# sboardnew.net
KiCad netlist of a schematic drawn in EAGLE
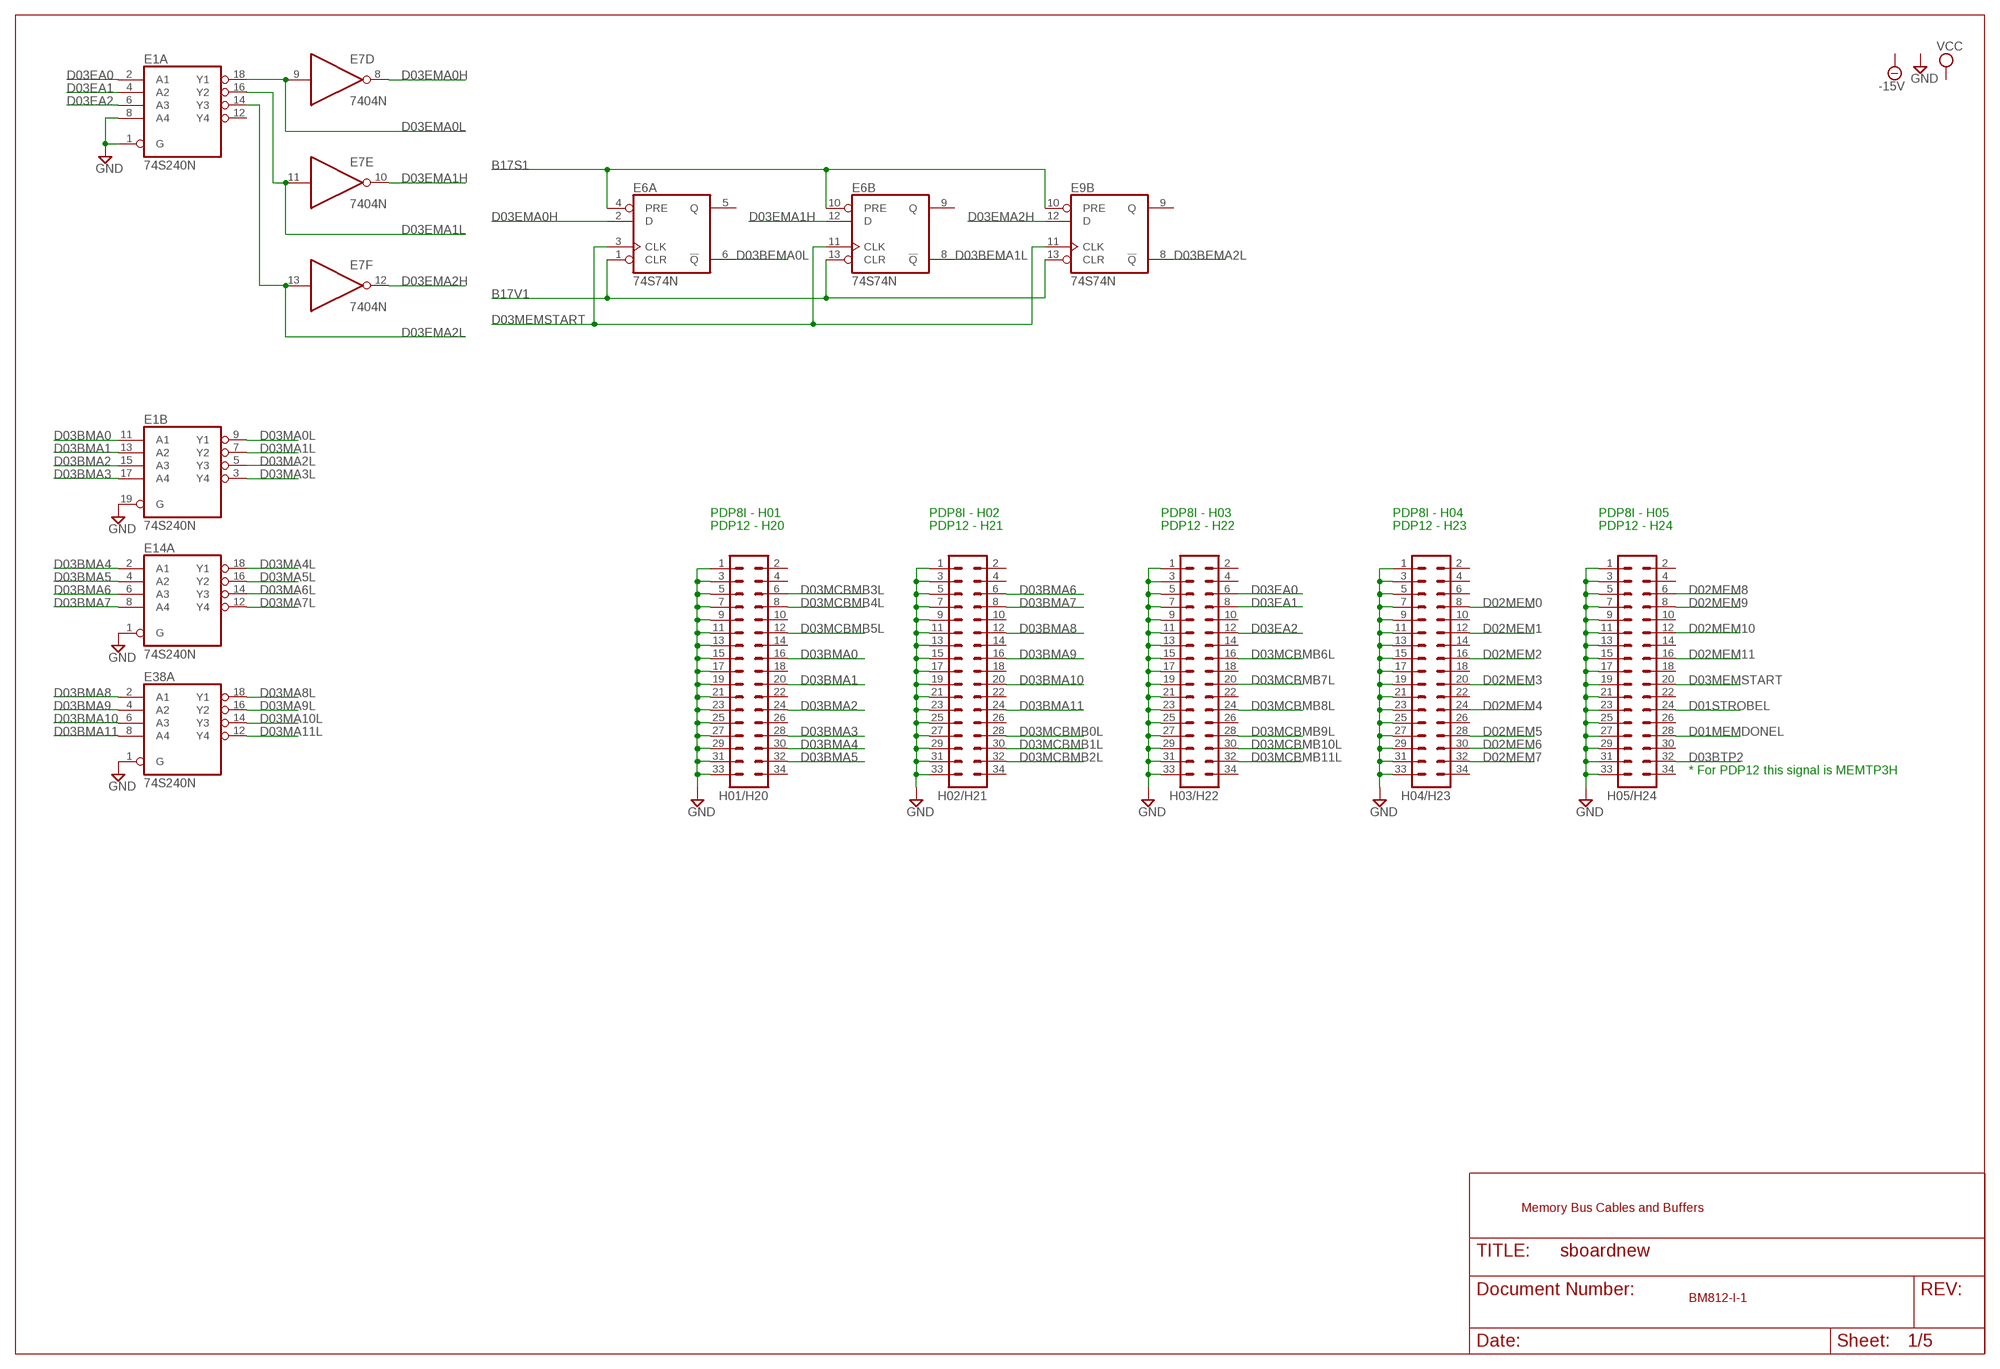
[diagram p0: schematic, sheet 1]
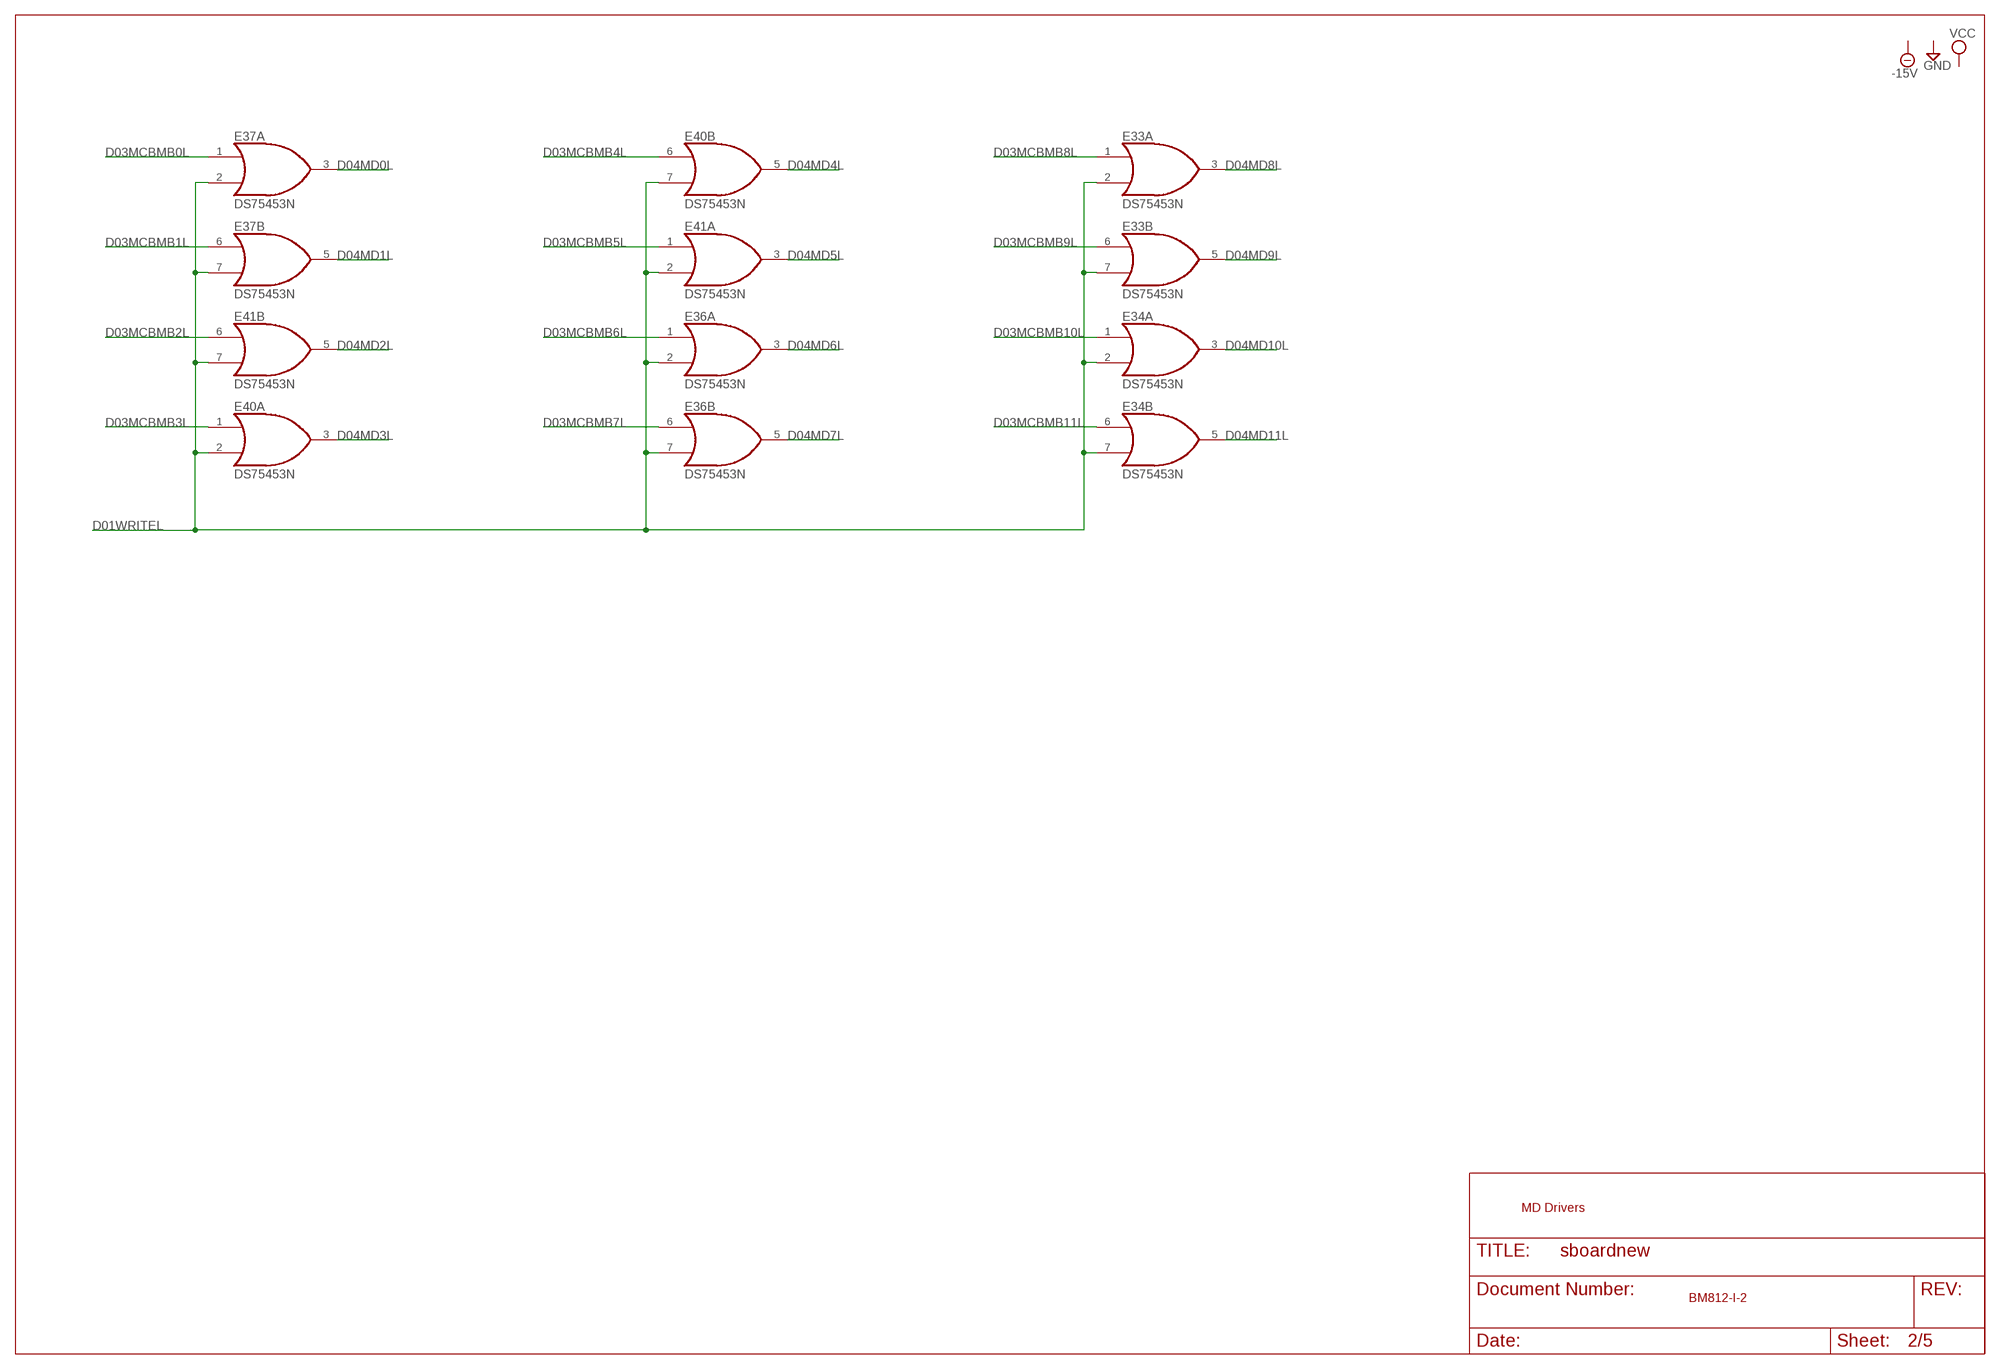
[diagram p1: schematic, sheet 2]
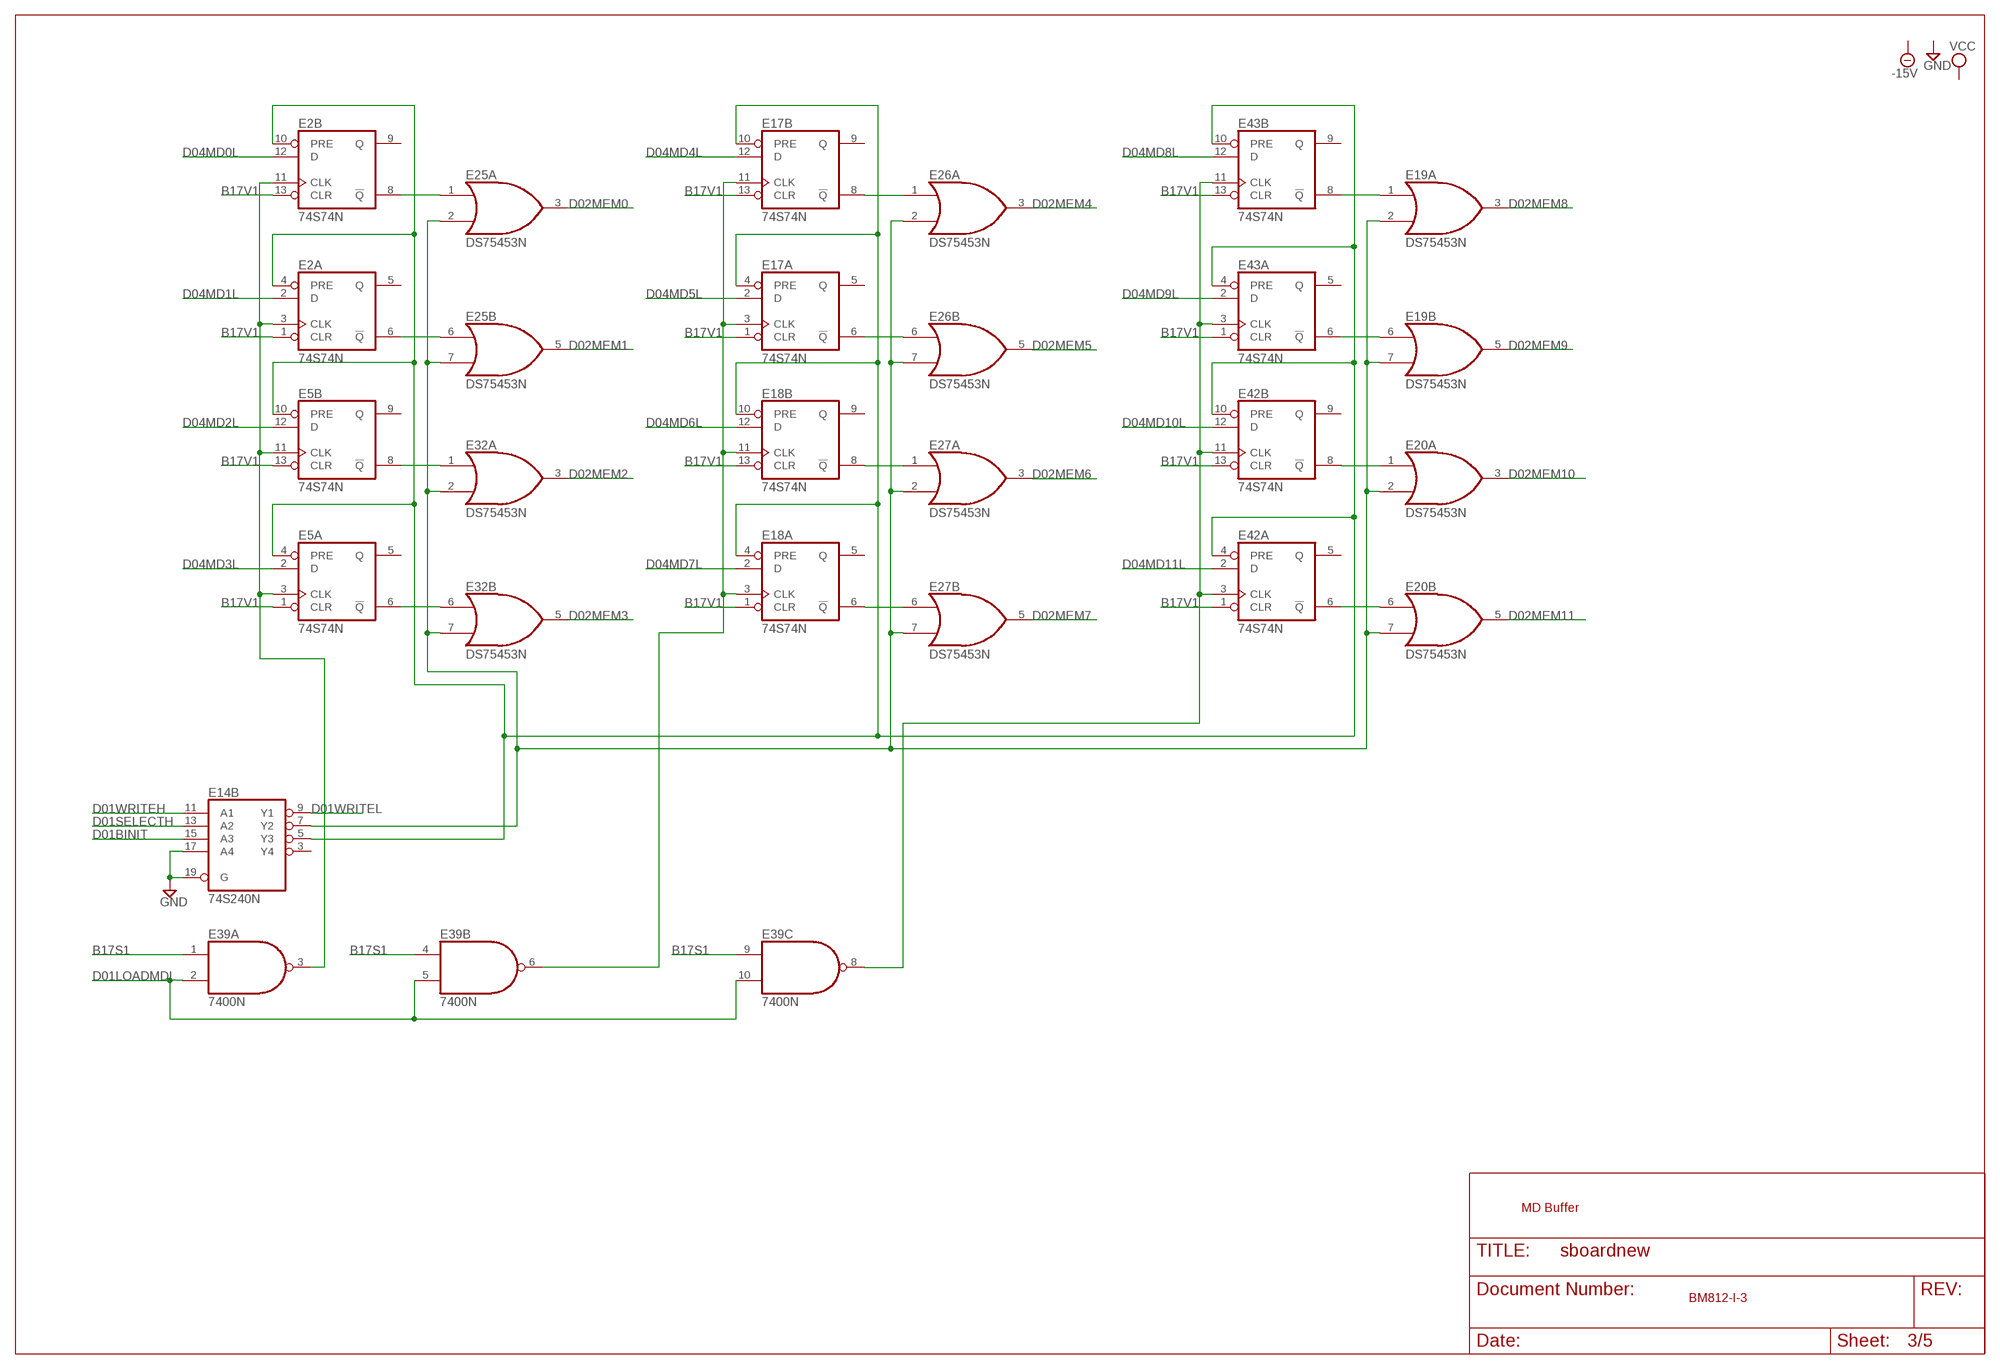
[diagram p2: schematic, sheet 3]
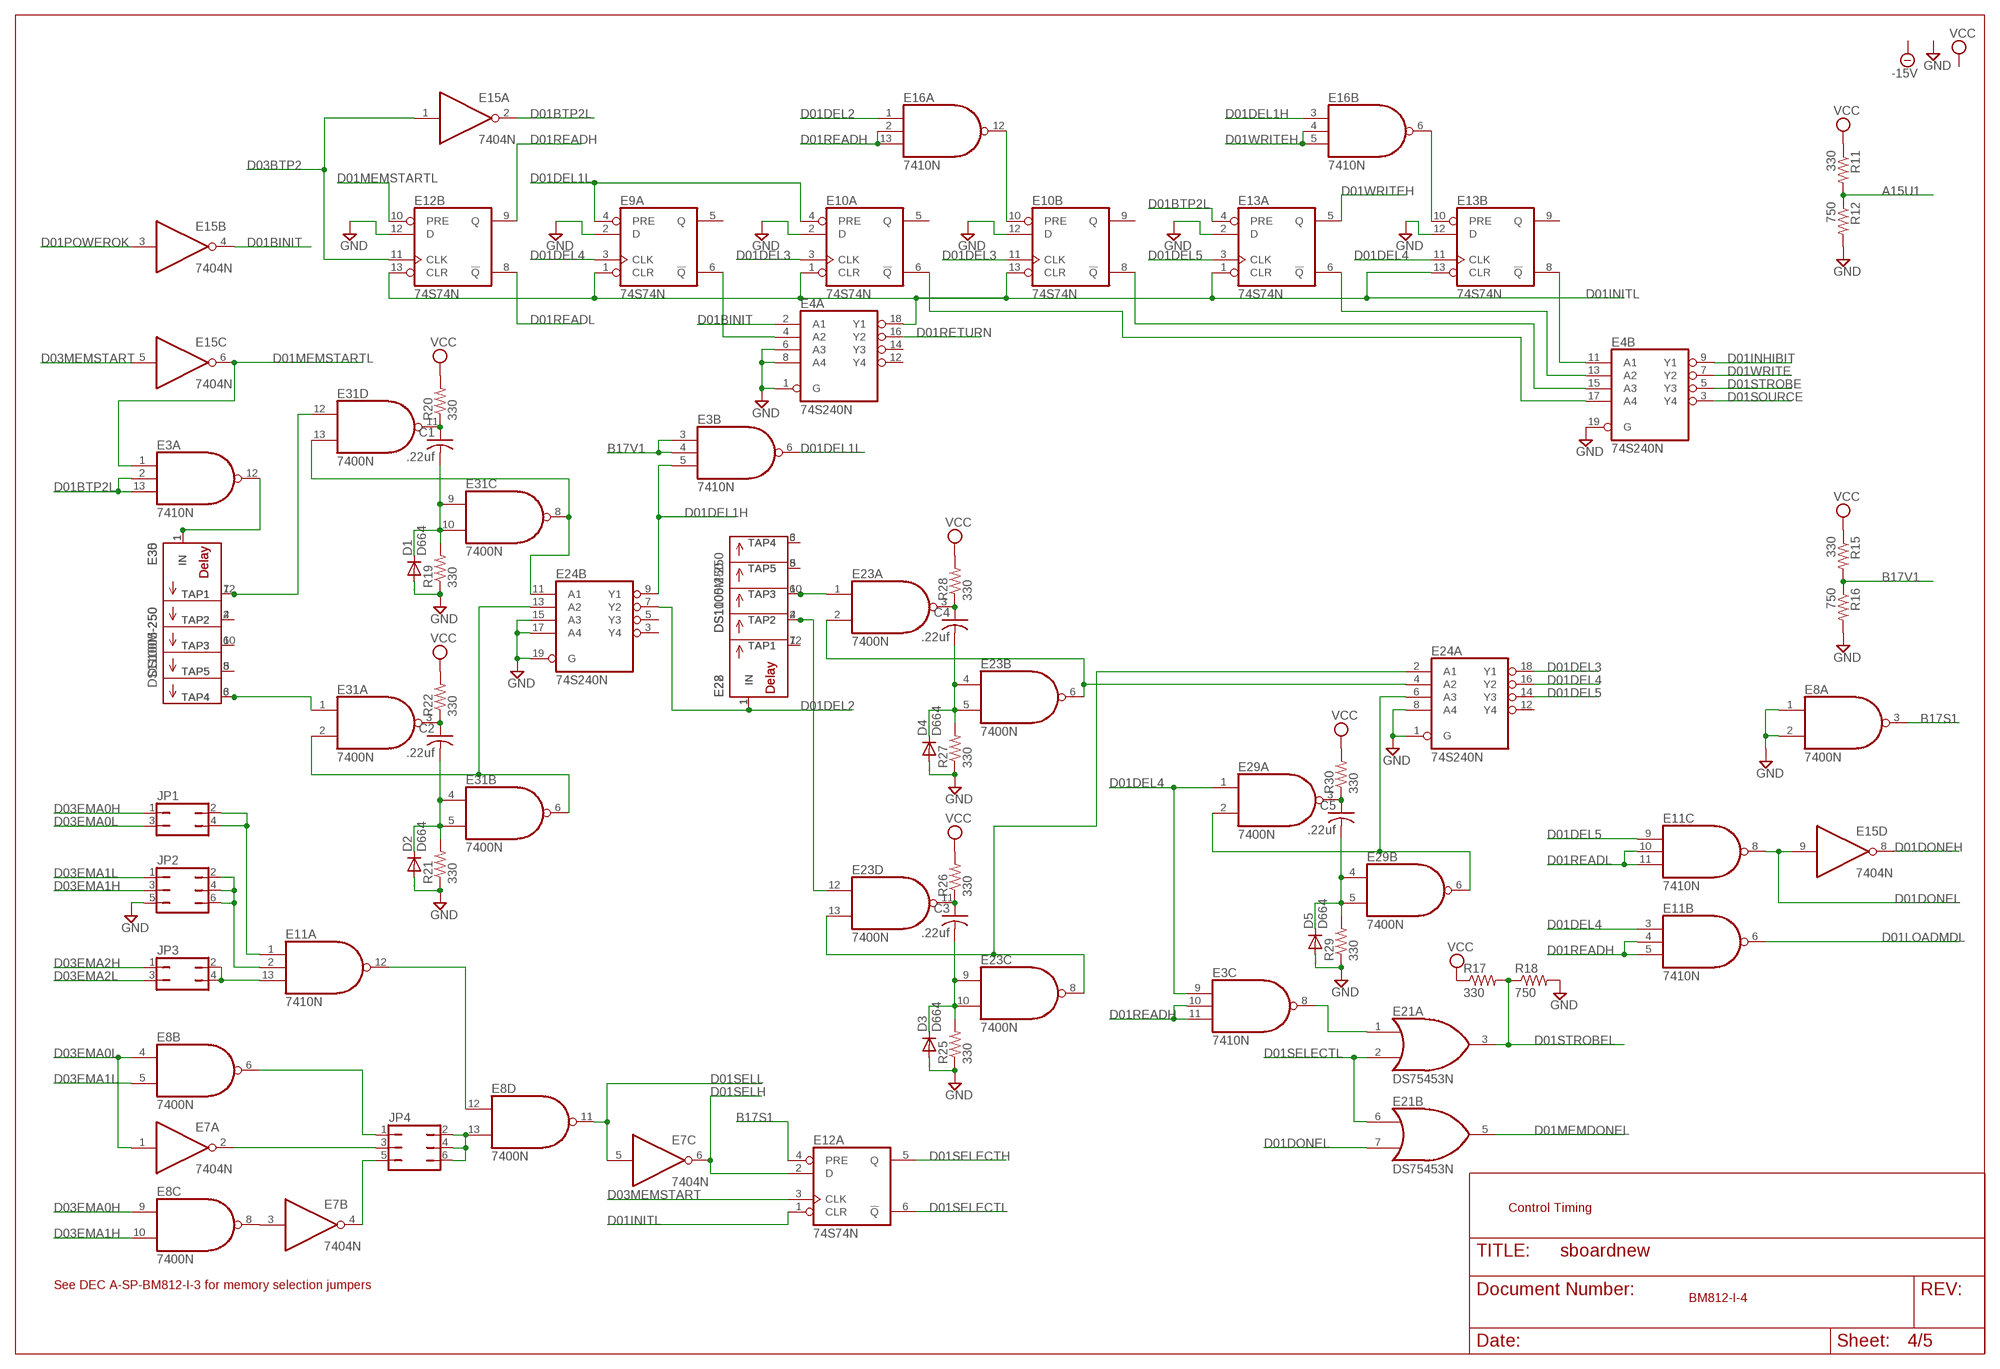
[diagram p3: schematic, sheet 4]
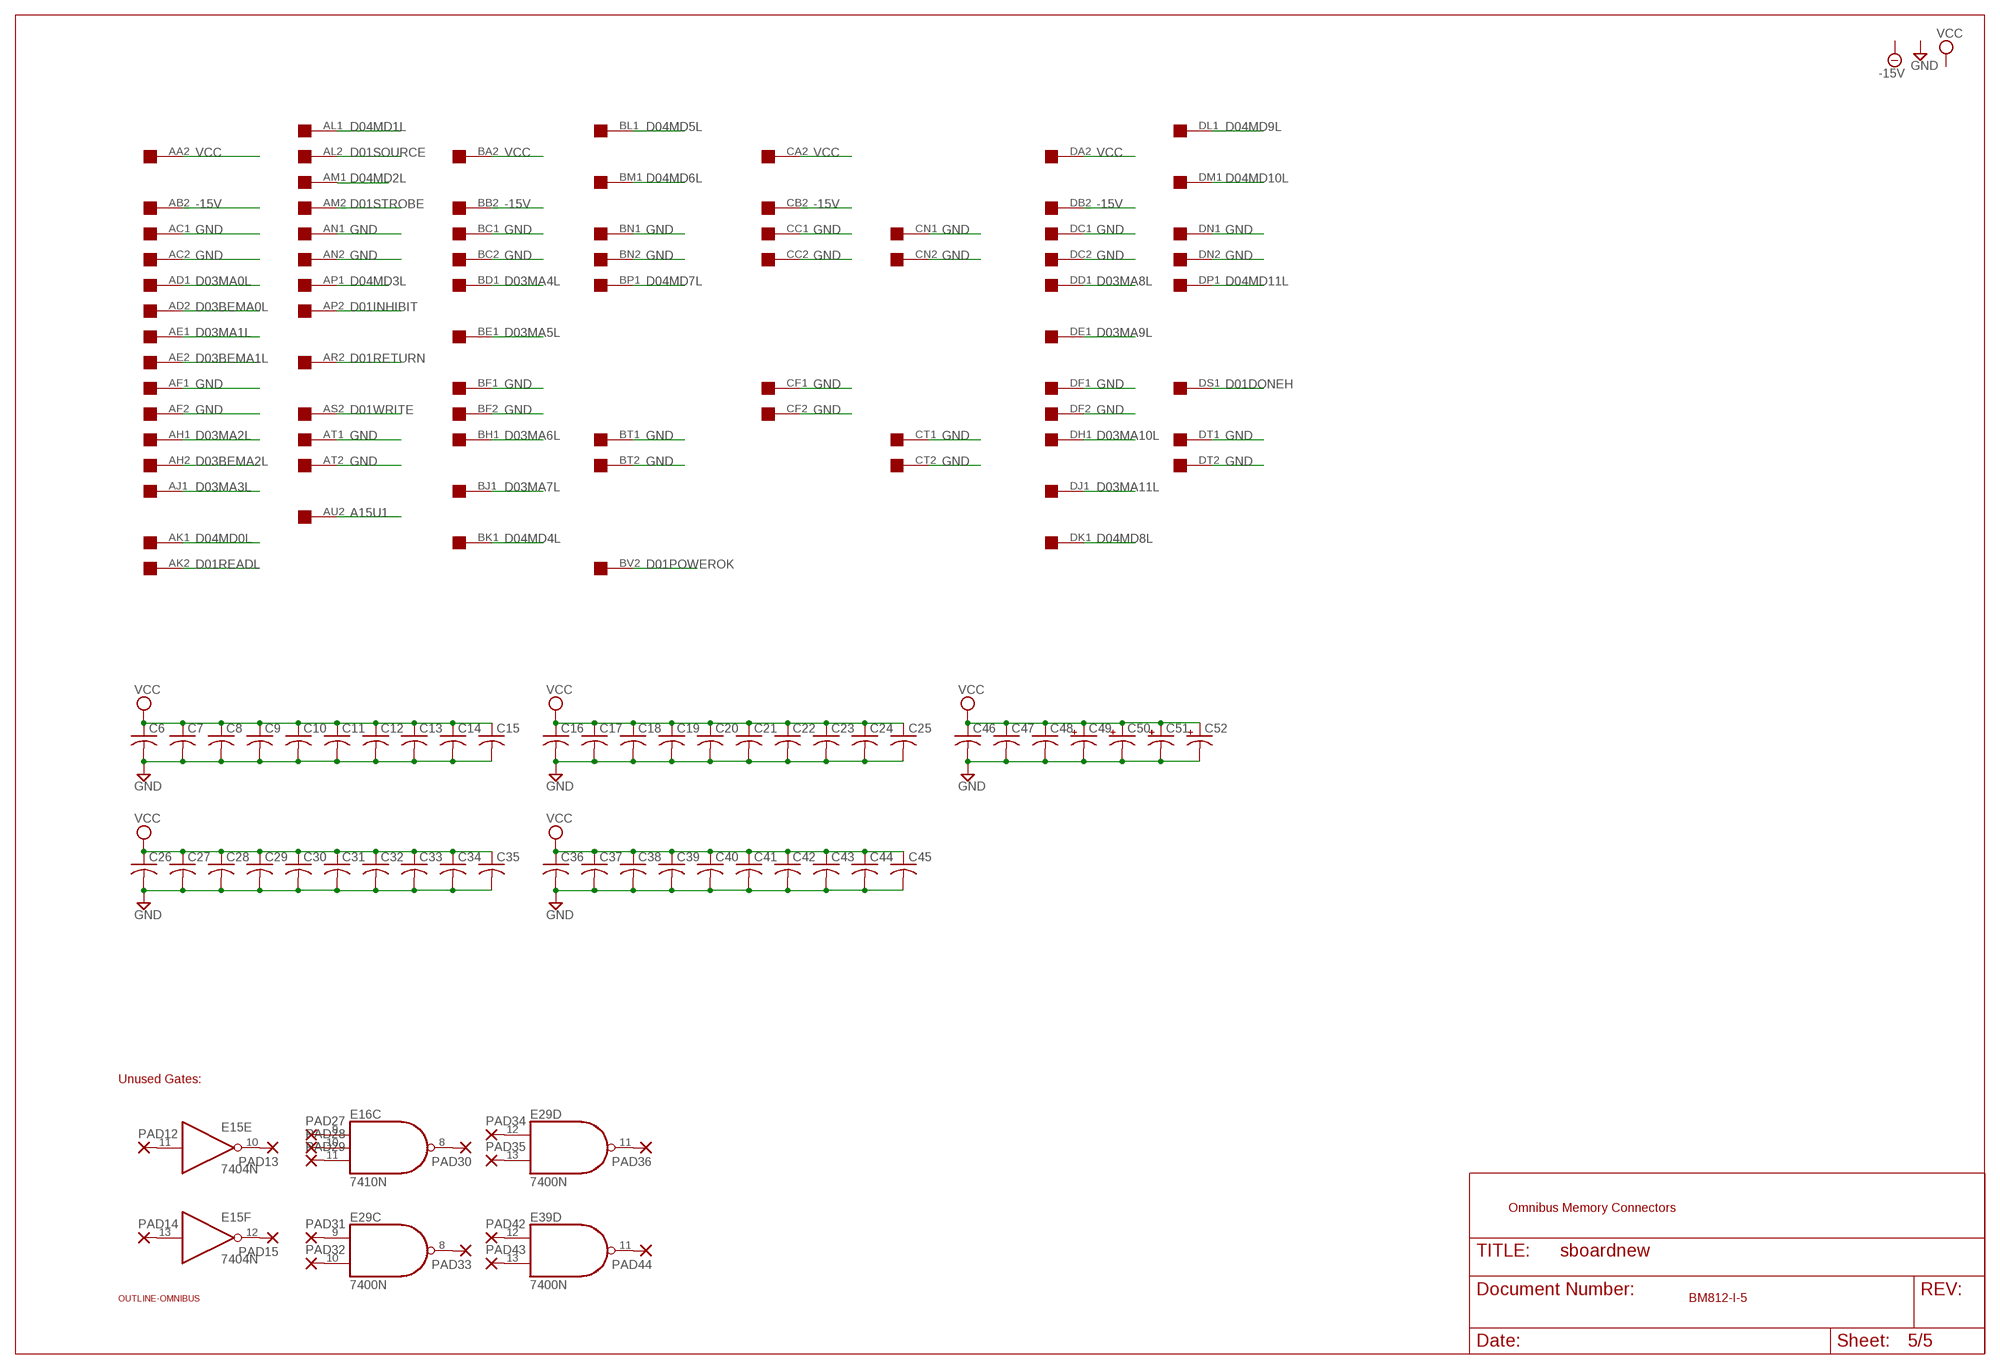
[diagram p4: schematic, sheet 5]

(export (version "E")
  (design (tool "Eeschema 10.0.6"))
  (components
    (comp (ref "E33")
      (value "DS75453N")
      (footprint "eagle-import:DIL08")
      (libsource (lib "eagle-import") (part "DS75453N"))
    )
    (comp (ref "E34")
      (value "DS75453N")
      (footprint "eagle-import:DIL08")
      (libsource (lib "eagle-import") (part "DS75453N"))
    )
    (comp (ref "E36")
      (value "DS75453N")
      (footprint "eagle-import:DIL08")
      (libsource (lib "eagle-import") (part "DS75453N"))
    )
    (comp (ref "E37")
      (value "DS75453N")
      (footprint "eagle-import:DIL08")
      (libsource (lib "eagle-import") (part "DS75453N"))
    )
    (comp (ref "E40")
      (value "DS75453N")
      (footprint "eagle-import:DIL08")
      (libsource (lib "eagle-import") (part "DS75453N"))
    )
    (comp (ref "E41")
      (value "DS75453N")
      (footprint "eagle-import:DIL08")
      (libsource (lib "eagle-import") (part "DS75453N"))
    )
    (comp (ref "E2")
      (value "74S74N")
      (footprint "eagle-import:DIL14")
      (libsource (lib "eagle-import") (part "7474NS"))
    )
    (comp (ref "E5")
      (value "74S74N")
      (footprint "eagle-import:DIL14")
      (libsource (lib "eagle-import") (part "7474NS"))
    )
    (comp (ref "E14")
      (value "74S240N")
      (footprint "eagle-import:DIL20")
      (libsource (lib "eagle-import") (part "74240NS"))
    )
    (comp (ref "E17")
      (value "74S74N")
      (footprint "eagle-import:DIL14")
      (libsource (lib "eagle-import") (part "7474NS"))
    )
    (comp (ref "E18")
      (value "74S74N")
      (footprint "eagle-import:DIL14")
      (libsource (lib "eagle-import") (part "7474NS"))
    )
    (comp (ref "E19")
      (value "DS75453N")
      (footprint "eagle-import:DIL08")
      (libsource (lib "eagle-import") (part "DS75453N"))
    )
    (comp (ref "E20")
      (value "DS75453N")
      (footprint "eagle-import:DIL08")
      (libsource (lib "eagle-import") (part "DS75453N"))
    )
    (comp (ref "E25")
      (value "DS75453N")
      (footprint "eagle-import:DIL08")
      (libsource (lib "eagle-import") (part "DS75453N"))
    )
    (comp (ref "E26")
      (value "DS75453N")
      (footprint "eagle-import:DIL08")
      (libsource (lib "eagle-import") (part "DS75453N"))
    )
    (comp (ref "E27")
      (value "DS75453N")
      (footprint "eagle-import:DIL08")
      (libsource (lib "eagle-import") (part "DS75453N"))
    )
    (comp (ref "E32")
      (value "DS75453N")
      (footprint "eagle-import:DIL08")
      (libsource (lib "eagle-import") (part "DS75453N"))
    )
    (comp (ref "E39")
      (value "7400N")
      (footprint "eagle-import:DIL14")
      (libsource (lib "eagle-import") (part "7400N"))
    )
    (comp (ref "E42")
      (value "74S74N")
      (footprint "eagle-import:DIL14")
      (libsource (lib "eagle-import") (part "7474NS"))
    )
    (comp (ref "E43")
      (value "74S74N")
      (footprint "eagle-import:DIL14")
      (libsource (lib "eagle-import") (part "7474NS"))
    )
    (comp (ref "C6")
      (value "C-US050-025X075")
      (footprint "eagle-import:C050-025X075")
      (libsource (lib "eagle-import") (part "C-US050-025X075"))
    )
    (comp (ref "C7")
      (value "C-US050-025X075")
      (footprint "eagle-import:C050-025X075")
      (libsource (lib "eagle-import") (part "C-US050-025X075"))
    )
    (comp (ref "C8")
      (value "C-US050-025X075")
      (footprint "eagle-import:C050-025X075")
      (libsource (lib "eagle-import") (part "C-US050-025X075"))
    )
    (comp (ref "C9")
      (value "C-US050-025X075")
      (footprint "eagle-import:C050-025X075")
      (libsource (lib "eagle-import") (part "C-US050-025X075"))
    )
    (comp (ref "C10")
      (value "C-US050-025X075")
      (footprint "eagle-import:C050-025X075")
      (libsource (lib "eagle-import") (part "C-US050-025X075"))
    )
    (comp (ref "C11")
      (value "C-US050-025X075")
      (footprint "eagle-import:C050-025X075")
      (libsource (lib "eagle-import") (part "C-US050-025X075"))
    )
    (comp (ref "C12")
      (value "C-US050-025X075")
      (footprint "eagle-import:C050-025X075")
      (libsource (lib "eagle-import") (part "C-US050-025X075"))
    )
    (comp (ref "C13")
      (value "C-US050-025X075")
      (footprint "eagle-import:C050-025X075")
      (libsource (lib "eagle-import") (part "C-US050-025X075"))
    )
    (comp (ref "C14")
      (value "C-US050-025X075")
      (footprint "eagle-import:C050-025X075")
      (libsource (lib "eagle-import") (part "C-US050-025X075"))
    )
    (comp (ref "C15")
      (value "C-US050-025X075")
      (footprint "eagle-import:C050-025X075")
      (libsource (lib "eagle-import") (part "C-US050-025X075"))
    )
    (comp (ref "C16")
      (value "C-US050-025X075")
      (footprint "eagle-import:C050-025X075")
      (libsource (lib "eagle-import") (part "C-US050-025X075"))
    )
    (comp (ref "C17")
      (value "C-US050-025X075")
      (footprint "eagle-import:C050-025X075")
      (libsource (lib "eagle-import") (part "C-US050-025X075"))
    )
    (comp (ref "C18")
      (value "C-US050-025X075")
      (footprint "eagle-import:C050-025X075")
      (libsource (lib "eagle-import") (part "C-US050-025X075"))
    )
    (comp (ref "C19")
      (value "C-US050-025X075")
      (footprint "eagle-import:C050-025X075")
      (libsource (lib "eagle-import") (part "C-US050-025X075"))
    )
    (comp (ref "C20")
      (value "C-US050-025X075")
      (footprint "eagle-import:C050-025X075")
      (libsource (lib "eagle-import") (part "C-US050-025X075"))
    )
    (comp (ref "C21")
      (value "C-US050-025X075")
      (footprint "eagle-import:C050-025X075")
      (libsource (lib "eagle-import") (part "C-US050-025X075"))
    )
    (comp (ref "C22")
      (value "C-US050-025X075")
      (footprint "eagle-import:C050-025X075")
      (libsource (lib "eagle-import") (part "C-US050-025X075"))
    )
    (comp (ref "C23")
      (value "C-US050-025X075")
      (footprint "eagle-import:C050-025X075")
      (libsource (lib "eagle-import") (part "C-US050-025X075"))
    )
    (comp (ref "C24")
      (value "C-US050-025X075")
      (footprint "eagle-import:C050-025X075")
      (libsource (lib "eagle-import") (part "C-US050-025X075"))
    )
    (comp (ref "C25")
      (value "C-US050-025X075")
      (footprint "eagle-import:C050-025X075")
      (libsource (lib "eagle-import") (part "C-US050-025X075"))
    )
    (comp (ref "C26")
      (value "C-US050-025X075")
      (footprint "eagle-import:C050-025X075")
      (libsource (lib "eagle-import") (part "C-US050-025X075"))
    )
    (comp (ref "C27")
      (value "C-US050-025X075")
      (footprint "eagle-import:C050-025X075")
      (libsource (lib "eagle-import") (part "C-US050-025X075"))
    )
    (comp (ref "C28")
      (value "C-US050-025X075")
      (footprint "eagle-import:C050-025X075")
      (libsource (lib "eagle-import") (part "C-US050-025X075"))
    )
    (comp (ref "C29")
      (value "C-US050-025X075")
      (footprint "eagle-import:C050-025X075")
      (libsource (lib "eagle-import") (part "C-US050-025X075"))
    )
    (comp (ref "C30")
      (value "C-US050-025X075")
      (footprint "eagle-import:C050-025X075")
      (libsource (lib "eagle-import") (part "C-US050-025X075"))
    )
    (comp (ref "C31")
      (value "C-US050-025X075")
      (footprint "eagle-import:C050-025X075")
      (libsource (lib "eagle-import") (part "C-US050-025X075"))
    )
    (comp (ref "C32")
      (value "C-US050-025X075")
      (footprint "eagle-import:C050-025X075")
      (libsource (lib "eagle-import") (part "C-US050-025X075"))
    )
    (comp (ref "C33")
      (value "C-US050-025X075")
      (footprint "eagle-import:C050-025X075")
      (libsource (lib "eagle-import") (part "C-US050-025X075"))
    )
    (comp (ref "C34")
      (value "C-US050-025X075")
      (footprint "eagle-import:C050-025X075")
      (libsource (lib "eagle-import") (part "C-US050-025X075"))
    )
    (comp (ref "C35")
      (value "C-US050-025X075")
      (footprint "eagle-import:C050-025X075")
      (libsource (lib "eagle-import") (part "C-US050-025X075"))
    )
    (comp (ref "C36")
      (value "C-US050-025X075")
      (footprint "eagle-import:C050-025X075")
      (libsource (lib "eagle-import") (part "C-US050-025X075"))
    )
    (comp (ref "C37")
      (value "C-US050-025X075")
      (footprint "eagle-import:C050-025X075")
      (libsource (lib "eagle-import") (part "C-US050-025X075"))
    )
    (comp (ref "C38")
      (value "C-US050-025X075")
      (footprint "eagle-import:C050-025X075")
      (libsource (lib "eagle-import") (part "C-US050-025X075"))
    )
    (comp (ref "C39")
      (value "C-US050-025X075")
      (footprint "eagle-import:C050-025X075")
      (libsource (lib "eagle-import") (part "C-US050-025X075"))
    )
    (comp (ref "C40")
      (value "C-US050-025X075")
      (footprint "eagle-import:C050-025X075")
      (libsource (lib "eagle-import") (part "C-US050-025X075"))
    )
    (comp (ref "C41")
      (value "C-US050-025X075")
      (footprint "eagle-import:C050-025X075")
      (libsource (lib "eagle-import") (part "C-US050-025X075"))
    )
    (comp (ref "C42")
      (value "C-US050-025X075")
      (footprint "eagle-import:C050-025X075")
      (libsource (lib "eagle-import") (part "C-US050-025X075"))
    )
    (comp (ref "C43")
      (value "C-US050-025X075")
      (footprint "eagle-import:C050-025X075")
      (libsource (lib "eagle-import") (part "C-US050-025X075"))
    )
    (comp (ref "C44")
      (value "C-US050-025X075")
      (footprint "eagle-import:C050-025X075")
      (libsource (lib "eagle-import") (part "C-US050-025X075"))
    )
    (comp (ref "C45")
      (value "C-US050-025X075")
      (footprint "eagle-import:C050-025X075")
      (libsource (lib "eagle-import") (part "C-US050-025X075"))
    )
    (comp (ref "C46")
      (value "C-US050-025X075")
      (footprint "eagle-import:C050-025X075")
      (libsource (lib "eagle-import") (part "C-US050-025X075"))
    )
    (comp (ref "C47")
      (value "C-US050-025X075")
      (footprint "eagle-import:C050-025X075")
      (libsource (lib "eagle-import") (part "C-US050-025X075"))
    )
    (comp (ref "C48")
      (value "C-US050-025X075")
      (footprint "eagle-import:C050-025X075")
      (libsource (lib "eagle-import") (part "C-US050-025X075"))
    )
    (comp (ref "C49")
      (value "CPOL-USE22-6AXIAL")
      (footprint "eagle-import:E22-6")
      (libsource (lib "eagle-import") (part "CPOL-USE22-6AXIAL"))
    )
    (comp (ref "C50")
      (value "CPOL-USE22-6AXIAL")
      (footprint "eagle-import:E22-6")
      (libsource (lib "eagle-import") (part "CPOL-USE22-6AXIAL"))
    )
    (comp (ref "C51")
      (value "CPOL-USE22-6AXIAL")
      (footprint "eagle-import:E22-6")
      (libsource (lib "eagle-import") (part "CPOL-USE22-6AXIAL"))
    )
    (comp (ref "C52")
      (value "CPOL-USE22-6AXIAL")
      (footprint "eagle-import:E22-6")
      (libsource (lib "eagle-import") (part "CPOL-USE22-6AXIAL"))
    )
    (comp (ref "E15")
      (value "7404N")
      (footprint "eagle-import:DIL14")
      (libsource (lib "eagle-import") (part "7404N"))
    )
    (comp (ref "E16")
      (value "7410N")
      (footprint "eagle-import:DIL14")
      (libsource (lib "eagle-import") (part "7410N"))
    )
    (comp (ref "E29")
      (value "7400N")
      (footprint "eagle-import:DIL14")
      (libsource (lib "eagle-import") (part "7400N"))
    )
    (comp (ref "PAD12")
      (value "1,6/0,8")
      (footprint "eagle-import:1,6_0,8")
      (libsource (lib "eagle-import") (part "1,6/0,8"))
    )
    (comp (ref "PAD13")
      (value "1,6/0,8")
      (footprint "eagle-import:1,6_0,8")
      (libsource (lib "eagle-import") (part "1,6/0,8"))
    )
    (comp (ref "PAD14")
      (value "1,6/0,8")
      (footprint "eagle-import:1,6_0,8")
      (libsource (lib "eagle-import") (part "1,6/0,8"))
    )
    (comp (ref "PAD15")
      (value "1,6/0,8")
      (footprint "eagle-import:1,6_0,8")
      (libsource (lib "eagle-import") (part "1,6/0,8"))
    )
    (comp (ref "PAD27")
      (value "1,6/0,8")
      (footprint "eagle-import:1,6_0,8")
      (libsource (lib "eagle-import") (part "1,6/0,8"))
    )
    (comp (ref "PAD28")
      (value "1,6/0,8")
      (footprint "eagle-import:1,6_0,8")
      (libsource (lib "eagle-import") (part "1,6/0,8"))
    )
    (comp (ref "PAD29")
      (value "1,6/0,8")
      (footprint "eagle-import:1,6_0,8")
      (libsource (lib "eagle-import") (part "1,6/0,8"))
    )
    (comp (ref "PAD30")
      (value "1,6/0,8")
      (footprint "eagle-import:1,6_0,8")
      (libsource (lib "eagle-import") (part "1,6/0,8"))
    )
    (comp (ref "PAD31")
      (value "1,6/0,8")
      (footprint "eagle-import:1,6_0,8")
      (libsource (lib "eagle-import") (part "1,6/0,8"))
    )
    (comp (ref "PAD32")
      (value "1,6/0,8")
      (footprint "eagle-import:1,6_0,8")
      (libsource (lib "eagle-import") (part "1,6/0,8"))
    )
    (comp (ref "PAD33")
      (value "1,6/0,8")
      (footprint "eagle-import:1,6_0,8")
      (libsource (lib "eagle-import") (part "1,6/0,8"))
    )
    (comp (ref "PAD34")
      (value "1,6/0,8")
      (footprint "eagle-import:1,6_0,8")
      (libsource (lib "eagle-import") (part "1,6/0,8"))
    )
    (comp (ref "PAD35")
      (value "1,6/0,8")
      (footprint "eagle-import:1,6_0,8")
      (libsource (lib "eagle-import") (part "1,6/0,8"))
    )
    (comp (ref "PAD36")
      (value "1,6/0,8")
      (footprint "eagle-import:1,6_0,8")
      (libsource (lib "eagle-import") (part "1,6/0,8"))
    )
    (comp (ref "PAD42")
      (value "1,6/0,8")
      (footprint "eagle-import:1,6_0,8")
      (libsource (lib "eagle-import") (part "1,6/0,8"))
    )
    (comp (ref "PAD43")
      (value "1,6/0,8")
      (footprint "eagle-import:1,6_0,8")
      (libsource (lib "eagle-import") (part "1,6/0,8"))
    )
    (comp (ref "PAD44")
      (value "1,6/0,8")
      (footprint "eagle-import:1,6_0,8")
      (libsource (lib "eagle-import") (part "1,6/0,8"))
    )
    (comp (ref "U$1")
      (value "QUAD")
      (footprint "eagle-import:EDGE-CON8")
      (libsource (lib "eagle-import") (part "QUAD"))
    )
    (comp (ref "U$2")
      (value "OUTLINE-OMNIBUS")
      (footprint "eagle-import:OMNIBUS")
      (libsource (lib "eagle-import") (part "OUTLINE-OMNIBUS"))
    )
    (comp (ref "C1")
      (value ".22uf")
      (footprint "eagle-import:C050-025X075")
      (libsource (lib "eagle-import") (part "C-US050-025X075"))
    )
    (comp (ref "C2")
      (value ".22uf")
      (footprint "eagle-import:C050-025X075")
      (libsource (lib "eagle-import") (part "C-US050-025X075"))
    )
    (comp (ref "C3")
      (value ".22uf")
      (footprint "eagle-import:C050-025X075")
      (libsource (lib "eagle-import") (part "C-US050-025X075"))
    )
    (comp (ref "C4")
      (value ".22uf")
      (footprint "eagle-import:C050-025X075")
      (libsource (lib "eagle-import") (part "C-US050-025X075"))
    )
    (comp (ref "C5")
      (value ".22uf")
      (footprint "eagle-import:C050-025X075")
      (libsource (lib "eagle-import") (part "C-US050-025X075"))
    )
    (comp (ref "D1")
      (value "D664")
      (footprint "eagle-import:DO35-10")
      (libsource (lib "eagle-import") (part "1N4148DO35-10"))
    )
    (comp (ref "D2")
      (value "D664")
      (footprint "eagle-import:DO35-10")
      (libsource (lib "eagle-import") (part "1N4148DO35-10"))
    )
    (comp (ref "D3")
      (value "D664")
      (footprint "eagle-import:DO35-10")
      (libsource (lib "eagle-import") (part "1N4148DO35-10"))
    )
    (comp (ref "D4")
      (value "D664")
      (footprint "eagle-import:DO35-10")
      (libsource (lib "eagle-import") (part "1N4148DO35-10"))
    )
    (comp (ref "D5")
      (value "D664")
      (footprint "eagle-import:DO35-10")
      (libsource (lib "eagle-import") (part "1N4148DO35-10"))
    )
    (comp (ref "E3")
      (value "7410N")
      (footprint "eagle-import:DIL14")
      (libsource (lib "eagle-import") (part "7410N"))
    )
    (comp (ref "E4")
      (value "74S240N")
      (footprint "eagle-import:DIL20")
      (libsource (lib "eagle-import") (part "74240NS"))
    )
    (comp (ref "E7")
      (value "7404N")
      (footprint "eagle-import:DIL14")
      (libsource (lib "eagle-import") (part "7404N"))
    )
    (comp (ref "E8")
      (value "7400N")
      (footprint "eagle-import:DIL14")
      (libsource (lib "eagle-import") (part "7400N"))
    )
    (comp (ref "E9")
      (value "74S74N")
      (footprint "eagle-import:DIL14")
      (libsource (lib "eagle-import") (part "7474NS"))
    )
    (comp (ref "E10")
      (value "74S74N")
      (footprint "eagle-import:DIL14")
      (libsource (lib "eagle-import") (part "7474NS"))
    )
    (comp (ref "E11")
      (value "7410N")
      (footprint "eagle-import:DIL14")
      (libsource (lib "eagle-import") (part "7410N"))
    )
    (comp (ref "E12")
      (value "74S74N")
      (footprint "eagle-import:DIL14")
      (libsource (lib "eagle-import") (part "7474NS"))
    )
    (comp (ref "E13")
      (value "74S74N")
      (footprint "eagle-import:DIL14")
      (libsource (lib "eagle-import") (part "7474NS"))
    )
    (comp (ref "E21")
      (value "DS75453N")
      (footprint "eagle-import:DIL08")
      (libsource (lib "eagle-import") (part "DS75453N"))
    )
    (comp (ref "E22")
      (value "DS1100M-250")
      (footprint "eagle-import:DIL08")
      (libsource (lib "eagle-import") (part "MXD1000"))
    )
    (comp (ref "E23")
      (value "7400N")
      (footprint "eagle-import:DIL14")
      (libsource (lib "eagle-import") (part "7400N"))
    )
    (comp (ref "E24")
      (value "74S240N")
      (footprint "eagle-import:DIL20")
      (libsource (lib "eagle-import") (part "74240NS"))
    )
    (comp (ref "E28")
      (value "DS1005-250")
      (footprint "eagle-import:DIL14")
      (libsource (lib "eagle-import") (part "MXD1000P"))
    )
    (comp (ref "E30")
      (value "DS1005-250")
      (footprint "eagle-import:DIL14")
      (libsource (lib "eagle-import") (part "MXD1000P"))
    )
    (comp (ref "E31")
      (value "7400N")
      (footprint "eagle-import:DIL14")
      (libsource (lib "eagle-import") (part "7400N"))
    )
    (comp (ref "E35")
      (value "DS1100M-250")
      (footprint "eagle-import:DIL08")
      (libsource (lib "eagle-import") (part "MXD1000"))
    )
    (comp (ref "JP1")
      (value "JP2Q")
      (footprint "eagle-import:JP2Q")
      (libsource (lib "eagle-import") (part "JP2Q"))
    )
    (comp (ref "JP2")
      (value "JP3Q")
      (footprint "eagle-import:JP3Q")
      (libsource (lib "eagle-import") (part "JP3Q"))
    )
    (comp (ref "JP3")
      (value "JP2Q")
      (footprint "eagle-import:JP2Q")
      (libsource (lib "eagle-import") (part "JP2Q"))
    )
    (comp (ref "JP4")
      (value "JP3Q")
      (footprint "eagle-import:JP3Q")
      (libsource (lib "eagle-import") (part "JP3Q"))
    )
    (comp (ref "R11")
      (value "330")
      (footprint "eagle-import:0207_10")
      (libsource (lib "eagle-import") (part "R-US_0207/10"))
    )
    (comp (ref "R12")
      (value "750")
      (footprint "eagle-import:0207_10")
      (libsource (lib "eagle-import") (part "R-US_0207/10"))
    )
    (comp (ref "R15")
      (value "330")
      (footprint "eagle-import:0207_10")
      (libsource (lib "eagle-import") (part "R-US_0207/10"))
    )
    (comp (ref "R16")
      (value "750")
      (footprint "eagle-import:0207_10")
      (libsource (lib "eagle-import") (part "R-US_0207/10"))
    )
    (comp (ref "R17")
      (value "330")
      (footprint "eagle-import:0207_10")
      (libsource (lib "eagle-import") (part "R-US_0207/10"))
    )
    (comp (ref "R18")
      (value "750")
      (footprint "eagle-import:0207_10")
      (libsource (lib "eagle-import") (part "R-US_0207/10"))
    )
    (comp (ref "R19")
      (value "330")
      (footprint "eagle-import:0207_10")
      (libsource (lib "eagle-import") (part "R-US_0207/10"))
    )
    (comp (ref "R20")
      (value "330")
      (footprint "eagle-import:0207_10")
      (libsource (lib "eagle-import") (part "R-US_0207/10"))
    )
    (comp (ref "R21")
      (value "330")
      (footprint "eagle-import:0207_10")
      (libsource (lib "eagle-import") (part "R-US_0207/10"))
    )
    (comp (ref "R22")
      (value "330")
      (footprint "eagle-import:0207_10")
      (libsource (lib "eagle-import") (part "R-US_0207/10"))
    )
    (comp (ref "R25")
      (value "330")
      (footprint "eagle-import:0207_10")
      (libsource (lib "eagle-import") (part "R-US_0207/10"))
    )
    (comp (ref "R26")
      (value "330")
      (footprint "eagle-import:0207_10")
      (libsource (lib "eagle-import") (part "R-US_0207/10"))
    )
    (comp (ref "R27")
      (value "330")
      (footprint "eagle-import:0207_10")
      (libsource (lib "eagle-import") (part "R-US_0207/10"))
    )
    (comp (ref "R28")
      (value "330")
      (footprint "eagle-import:0207_10")
      (libsource (lib "eagle-import") (part "R-US_0207/10"))
    )
    (comp (ref "R29")
      (value "330")
      (footprint "eagle-import:0207_10")
      (libsource (lib "eagle-import") (part "R-US_0207/10"))
    )
    (comp (ref "R30")
      (value "330")
      (footprint "eagle-import:0207_10")
      (libsource (lib "eagle-import") (part "R-US_0207/10"))
    )
    (comp (ref "E1")
      (value "74S240N")
      (footprint "eagle-import:DIL20")
      (libsource (lib "eagle-import") (part "74240NS"))
    )
    (comp (ref "E6")
      (value "74S74N")
      (footprint "eagle-import:DIL14")
      (libsource (lib "eagle-import") (part "7474NS"))
    )
    (comp (ref "E38")
      (value "74S240N")
      (footprint "eagle-import:DIL20")
      (libsource (lib "eagle-import") (part "74240NS"))
    )
    (comp (ref "H01/H20")
      (value "MA17-2")
      (footprint "eagle-import:MA17-2")
      (libsource (lib "eagle-import") (part "MA17-2"))
    )
    (comp (ref "H02/H21")
      (value "MA17-2")
      (footprint "eagle-import:MA17-2")
      (libsource (lib "eagle-import") (part "MA17-2"))
    )
    (comp (ref "H03/H22")
      (value "MA17-2")
      (footprint "eagle-import:MA17-2")
      (libsource (lib "eagle-import") (part "MA17-2"))
    )
    (comp (ref "H04/H23")
      (value "MA17-2")
      (footprint "eagle-import:MA17-2")
      (libsource (lib "eagle-import") (part "MA17-2"))
    )
    (comp (ref "H05/H24")
      (value "MA17-2")
      (footprint "eagle-import:MA17-2")
      (libsource (lib "eagle-import") (part "MA17-2"))
    )
  )
  (nets
    (net (code "1") (name "-15V") (class "Default")
      (node (ref "U$1") (pin "AB2") (pinfunction "1_AB2") (pintype "bidirectional"))
      (node (ref "U$1") (pin "BB2") (pinfunction "1_BB2") (pintype "bidirectional"))
      (node (ref "U$1") (pin "CB2") (pinfunction "1_CB2") (pintype "bidirectional"))
      (node (ref "U$1") (pin "DB2") (pinfunction "1_DB2") (pintype "bidirectional"))
    )
    (net (code "2") (name "A15U1") (class "Default")
      (node (ref "R11") (pin "2") (pinfunction "2_2") (pintype "passive"))
      (node (ref "R12") (pin "1") (pinfunction "1_1") (pintype "passive"))
      (node (ref "U$1") (pin "AU2") (pinfunction "1_AU2") (pintype "bidirectional"))
    )
    (net (code "3") (name "B17S1") (class "Default")
      (node (ref "E12") (pin "4") (pinfunction "PRE_4") (pintype "input"))
      (node (ref "E39") (pin "1") (pinfunction "I0_1") (pintype "input"))
      (node (ref "E39") (pin "4") (pinfunction "I0_4") (pintype "input"))
      (node (ref "E39") (pin "9") (pinfunction "I0_9") (pintype "input"))
      (node (ref "E6") (pin "10") (pinfunction "PRE_10") (pintype "input"))
      (node (ref "E6") (pin "4") (pinfunction "PRE_4") (pintype "input"))
      (node (ref "E8") (pin "3") (pinfunction "O_3") (pintype "output"))
      (node (ref "E9") (pin "10") (pinfunction "PRE_10") (pintype "input"))
    )
    (net (code "4") (name "B17V1") (class "Default")
      (node (ref "E17") (pin "1") (pinfunction "CLR_1") (pintype "input"))
      (node (ref "E17") (pin "13") (pinfunction "CLR_13") (pintype "input"))
      (node (ref "E18") (pin "1") (pinfunction "CLR_1") (pintype "input"))
      (node (ref "E18") (pin "13") (pinfunction "CLR_13") (pintype "input"))
      (node (ref "E2") (pin "1") (pinfunction "CLR_1") (pintype "input"))
      (node (ref "E2") (pin "13") (pinfunction "CLR_13") (pintype "input"))
      (node (ref "E3") (pin "3") (pinfunction "I0_3") (pintype "input"))
      (node (ref "E3") (pin "4") (pinfunction "I1_4") (pintype "input"))
      (node (ref "E42") (pin "1") (pinfunction "CLR_1") (pintype "input"))
      (node (ref "E42") (pin "13") (pinfunction "CLR_13") (pintype "input"))
      (node (ref "E43") (pin "1") (pinfunction "CLR_1") (pintype "input"))
      (node (ref "E43") (pin "13") (pinfunction "CLR_13") (pintype "input"))
      (node (ref "E5") (pin "1") (pinfunction "CLR_1") (pintype "input"))
      (node (ref "E5") (pin "13") (pinfunction "CLR_13") (pintype "input"))
      (node (ref "E6") (pin "1") (pinfunction "CLR_1") (pintype "input"))
      (node (ref "E6") (pin "13") (pinfunction "CLR_13") (pintype "input"))
      (node (ref "E9") (pin "13") (pinfunction "CLR_13") (pintype "input"))
      (node (ref "R15") (pin "2") (pinfunction "2_2") (pintype "passive"))
      (node (ref "R16") (pin "1") (pinfunction "1_1") (pintype "passive"))
    )
    (net (code "5") (name "D01BINIT") (class "Default")
      (node (ref "E14") (pin "15") (pinfunction "A3_15") (pintype "input"))
      (node (ref "E15") (pin "4") (pinfunction "O_4") (pintype "output"))
      (node (ref "E4") (pin "2") (pinfunction "A1_2") (pintype "input"))
    )
    (net (code "6") (name "D01BTP2L") (class "Default")
      (node (ref "E13") (pin "4") (pinfunction "PRE_4") (pintype "input"))
      (node (ref "E15") (pin "2") (pinfunction "O_2") (pintype "output"))
      (node (ref "E3") (pin "13") (pinfunction "I2_13") (pintype "input"))
      (node (ref "E3") (pin "2") (pinfunction "I1_2") (pintype "input"))
    )
    (net (code "7") (name "D01DEL1H") (class "Default")
      (node (ref "E16") (pin "3") (pinfunction "I0_3") (pintype "input"))
      (node (ref "E24") (pin "9") (pinfunction "Y1_9") (pintype "tri_state"))
      (node (ref "E3") (pin "5") (pinfunction "I2_5") (pintype "input"))
    )
    (net (code "8") (name "D01DEL1L") (class "Default")
      (node (ref "E10") (pin "4") (pinfunction "PRE_4") (pintype "input"))
      (node (ref "E3") (pin "6") (pinfunction "O_6") (pintype "output"))
      (node (ref "E9") (pin "4") (pinfunction "PRE_4") (pintype "input"))
    )
    (net (code "9") (name "D01DEL2") (class "Default")
      (node (ref "E16") (pin "1") (pinfunction "I0_1") (pintype "input"))
      (node (ref "E22") (pin "1") (pinfunction "IN_1") (pintype "input"))
      (node (ref "E24") (pin "7") (pinfunction "Y2_7") (pintype "tri_state"))
      (node (ref "E28") (pin "1") (pinfunction "IN_1") (pintype "input"))
    )
    (net (code "10") (name "D01DEL3") (class "Default")
      (node (ref "E10") (pin "11") (pinfunction "CLK_11") (pintype "input"))
      (node (ref "E10") (pin "3") (pinfunction "CLK_3") (pintype "input"))
      (node (ref "E24") (pin "18") (pinfunction "Y1_18") (pintype "tri_state"))
    )
    (net (code "11") (name "D01DEL4") (class "Default")
      (node (ref "E11") (pin "3") (pinfunction "I0_3") (pintype "input"))
      (node (ref "E13") (pin "11") (pinfunction "CLK_11") (pintype "input"))
      (node (ref "E24") (pin "16") (pinfunction "Y2_16") (pintype "tri_state"))
      (node (ref "E29") (pin "1") (pinfunction "I0_1") (pintype "input"))
      (node (ref "E3") (pin "9") (pinfunction "I0_9") (pintype "input"))
      (node (ref "E9") (pin "3") (pinfunction "CLK_3") (pintype "input"))
    )
    (net (code "12") (name "D01DEL5") (class "Default")
      (node (ref "E11") (pin "9") (pinfunction "I0_9") (pintype "input"))
      (node (ref "E13") (pin "3") (pinfunction "CLK_3") (pintype "input"))
      (node (ref "E24") (pin "14") (pinfunction "Y3_14") (pintype "tri_state"))
    )
    (net (code "13") (name "D01DONEH") (class "Default")
      (node (ref "E15") (pin "8") (pinfunction "O_8") (pintype "output"))
      (node (ref "U$1") (pin "DS1") (pinfunction "1_DS1") (pintype "bidirectional"))
    )
    (net (code "14") (name "D01DONEL") (class "Default")
      (node (ref "E11") (pin "8") (pinfunction "O_8") (pintype "output"))
      (node (ref "E15") (pin "9") (pinfunction "I_9") (pintype "input"))
      (node (ref "E21") (pin "7") (pinfunction "I1_7") (pintype "input"))
    )
    (net (code "15") (name "D01INHIBIT") (class "Default")
      (node (ref "E4") (pin "9") (pinfunction "Y1_9") (pintype "tri_state"))
      (node (ref "U$1") (pin "AP2") (pinfunction "1_AP2") (pintype "bidirectional"))
    )
    (net (code "16") (name "D01INITL") (class "Default")
      (node (ref "E10") (pin "1") (pinfunction "CLR_1") (pintype "input"))
      (node (ref "E10") (pin "13") (pinfunction "CLR_13") (pintype "input"))
      (node (ref "E12") (pin "1") (pinfunction "CLR_1") (pintype "input"))
      (node (ref "E12") (pin "13") (pinfunction "CLR_13") (pintype "input"))
      (node (ref "E13") (pin "1") (pinfunction "CLR_1") (pintype "input"))
      (node (ref "E13") (pin "13") (pinfunction "CLR_13") (pintype "input"))
      (node (ref "E4") (pin "18") (pinfunction "Y1_18") (pintype "tri_state"))
      (node (ref "E9") (pin "1") (pinfunction "CLR_1") (pintype "input"))
    )
    (net (code "17") (name "D01LOADMDL") (class "Default")
      (node (ref "E11") (pin "6") (pinfunction "O_6") (pintype "output"))
      (node (ref "E39") (pin "10") (pinfunction "I1_10") (pintype "input"))
      (node (ref "E39") (pin "2") (pinfunction "I1_2") (pintype "input"))
      (node (ref "E39") (pin "5") (pinfunction "I1_5") (pintype "input"))
    )
    (net (code "18") (name "D01MEMDONEL") (class "Default")
      (node (ref "E21") (pin "5") (pinfunction "O_5") (pintype "open_collector"))
      (node (ref "H05/H24") (pin "28") (pinfunction "28_28") (pintype "passive"))
    )
    (net (code "19") (name "D01MEMSTARTL") (class "Default")
      (node (ref "E12") (pin "10") (pinfunction "PRE_10") (pintype "input"))
      (node (ref "E15") (pin "6") (pinfunction "O_6") (pintype "output"))
      (node (ref "E3") (pin "1") (pinfunction "I0_1") (pintype "input"))
    )
    (net (code "20") (name "D01POWEROK") (class "Default")
      (node (ref "E15") (pin "3") (pinfunction "I_3") (pintype "input"))
      (node (ref "U$1") (pin "BV2") (pinfunction "1_BV2") (pintype "bidirectional"))
    )
    (net (code "21") (name "D01READH") (class "Default")
      (node (ref "E11") (pin "4") (pinfunction "I1_4") (pintype "input"))
      (node (ref "E11") (pin "5") (pinfunction "I2_5") (pintype "input"))
      (node (ref "E12") (pin "9") (pinfunction "Q_9") (pintype "output"))
      (node (ref "E16") (pin "13") (pinfunction "I2_13") (pintype "input"))
      (node (ref "E16") (pin "2") (pinfunction "I1_2") (pintype "input"))
      (node (ref "E3") (pin "10") (pinfunction "I1_10") (pintype "input"))
      (node (ref "E3") (pin "11") (pinfunction "I2_11") (pintype "input"))
    )
    (net (code "22") (name "D01READL") (class "Default")
      (node (ref "E11") (pin "10") (pinfunction "I1_10") (pintype "input"))
      (node (ref "E11") (pin "11") (pinfunction "I2_11") (pintype "input"))
      (node (ref "E12") (pin "8") (pinfunction "~{Q}_8") (pintype "output"))
      (node (ref "U$1") (pin "AK2") (pinfunction "1_AK2") (pintype "bidirectional"))
    )
    (net (code "23") (name "D01RETURN") (class "Default")
      (node (ref "E4") (pin "16") (pinfunction "Y2_16") (pintype "tri_state"))
      (node (ref "U$1") (pin "AR2") (pinfunction "1_AR2") (pintype "bidirectional"))
    )
    (net (code "24") (name "D01SELECTH") (class "Default")
      (node (ref "E12") (pin "5") (pinfunction "Q_5") (pintype "output"))
      (node (ref "E14") (pin "13") (pinfunction "A2_13") (pintype "input"))
    )
    (net (code "25") (name "D01SELECTL") (class "Default")
      (node (ref "E12") (pin "6") (pinfunction "~{Q}_6") (pintype "output"))
      (node (ref "E21") (pin "2") (pinfunction "I1_2") (pintype "input"))
      (node (ref "E21") (pin "6") (pinfunction "I0_6") (pintype "input"))
    )
    (net (code "26") (name "D01SELH") (class "Default")
      (node (ref "E12") (pin "2") (pinfunction "D_2") (pintype "input"))
      (node (ref "E7") (pin "6") (pinfunction "O_6") (pintype "output"))
    )
    (net (code "27") (name "D01SELL") (class "Default")
      (node (ref "E7") (pin "5") (pinfunction "I_5") (pintype "input"))
      (node (ref "E8") (pin "11") (pinfunction "O_11") (pintype "output"))
    )
    (net (code "28") (name "D01SOURCE") (class "Default")
      (node (ref "E4") (pin "3") (pinfunction "Y4_3") (pintype "tri_state"))
      (node (ref "U$1") (pin "AL2") (pinfunction "1_AL2") (pintype "bidirectional"))
    )
    (net (code "29") (name "D01STROBE") (class "Default")
      (node (ref "E4") (pin "5") (pinfunction "Y3_5") (pintype "tri_state"))
      (node (ref "U$1") (pin "AM2") (pinfunction "1_AM2") (pintype "bidirectional"))
    )
    (net (code "30") (name "D01STROBEL") (class "Default")
      (node (ref "E21") (pin "3") (pinfunction "O_3") (pintype "open_collector"))
      (node (ref "H05/H24") (pin "24") (pinfunction "24_24") (pintype "passive"))
      (node (ref "R17") (pin "2") (pinfunction "2_2") (pintype "passive"))
      (node (ref "R18") (pin "1") (pinfunction "1_1") (pintype "passive"))
    )
    (net (code "31") (name "D01WRITE") (class "Default")
      (node (ref "E4") (pin "7") (pinfunction "Y2_7") (pintype "tri_state"))
      (node (ref "U$1") (pin "AS2") (pinfunction "1_AS2") (pintype "bidirectional"))
    )
    (net (code "32") (name "D01WRITEH") (class "Default")
      (node (ref "E13") (pin "5") (pinfunction "Q_5") (pintype "output"))
      (node (ref "E14") (pin "11") (pinfunction "A1_11") (pintype "input"))
      (node (ref "E16") (pin "4") (pinfunction "I1_4") (pintype "input"))
      (node (ref "E16") (pin "5") (pinfunction "I2_5") (pintype "input"))
    )
    (net (code "33") (name "D01WRITEL") (class "Default")
      (node (ref "E14") (pin "9") (pinfunction "Y1_9") (pintype "tri_state"))
      (node (ref "E33") (pin "2") (pinfunction "I1_2") (pintype "input"))
      (node (ref "E33") (pin "7") (pinfunction "I1_7") (pintype "input"))
      (node (ref "E34") (pin "2") (pinfunction "I1_2") (pintype "input"))
      (node (ref "E34") (pin "7") (pinfunction "I1_7") (pintype "input"))
      (node (ref "E36") (pin "2") (pinfunction "I1_2") (pintype "input"))
      (node (ref "E36") (pin "7") (pinfunction "I1_7") (pintype "input"))
      (node (ref "E37") (pin "2") (pinfunction "I1_2") (pintype "input"))
      (node (ref "E37") (pin "7") (pinfunction "I1_7") (pintype "input"))
      (node (ref "E40") (pin "2") (pinfunction "I1_2") (pintype "input"))
      (node (ref "E40") (pin "7") (pinfunction "I1_7") (pintype "input"))
      (node (ref "E41") (pin "2") (pinfunction "I1_2") (pintype "input"))
      (node (ref "E41") (pin "7") (pinfunction "I1_7") (pintype "input"))
    )
    (net (code "34") (name "D02MEM0") (class "Default")
      (node (ref "E25") (pin "3") (pinfunction "O_3") (pintype "open_collector"))
      (node (ref "H04/H23") (pin "8") (pinfunction "8_8") (pintype "passive"))
    )
    (net (code "35") (name "D02MEM1") (class "Default")
      (node (ref "E25") (pin "5") (pinfunction "O_5") (pintype "open_collector"))
      (node (ref "H04/H23") (pin "12") (pinfunction "12_12") (pintype "passive"))
    )
    (net (code "36") (name "D02MEM2") (class "Default")
      (node (ref "E32") (pin "3") (pinfunction "O_3") (pintype "open_collector"))
      (node (ref "H04/H23") (pin "16") (pinfunction "16_16") (pintype "passive"))
    )
    (net (code "37") (name "D02MEM3") (class "Default")
      (node (ref "E32") (pin "5") (pinfunction "O_5") (pintype "open_collector"))
      (node (ref "H04/H23") (pin "20") (pinfunction "20_20") (pintype "passive"))
    )
    (net (code "38") (name "D02MEM4") (class "Default")
      (node (ref "E26") (pin "3") (pinfunction "O_3") (pintype "open_collector"))
      (node (ref "H04/H23") (pin "24") (pinfunction "24_24") (pintype "passive"))
    )
    (net (code "39") (name "D02MEM5") (class "Default")
      (node (ref "E26") (pin "5") (pinfunction "O_5") (pintype "open_collector"))
      (node (ref "H04/H23") (pin "28") (pinfunction "28_28") (pintype "passive"))
    )
    (net (code "40") (name "D02MEM6") (class "Default")
      (node (ref "E27") (pin "3") (pinfunction "O_3") (pintype "open_collector"))
      (node (ref "H04/H23") (pin "30") (pinfunction "30_30") (pintype "passive"))
    )
    (net (code "41") (name "D02MEM7") (class "Default")
      (node (ref "E27") (pin "5") (pinfunction "O_5") (pintype "open_collector"))
      (node (ref "H04/H23") (pin "32") (pinfunction "32_32") (pintype "passive"))
    )
    (net (code "42") (name "D02MEM8") (class "Default")
      (node (ref "E19") (pin "3") (pinfunction "O_3") (pintype "open_collector"))
      (node (ref "H05/H24") (pin "6") (pinfunction "6_6") (pintype "passive"))
    )
    (net (code "43") (name "D02MEM9") (class "Default")
      (node (ref "E19") (pin "5") (pinfunction "O_5") (pintype "open_collector"))
      (node (ref "H05/H24") (pin "8") (pinfunction "8_8") (pintype "passive"))
    )
    (net (code "44") (name "D02MEM10") (class "Default")
      (node (ref "E20") (pin "3") (pinfunction "O_3") (pintype "open_collector"))
      (node (ref "H05/H24") (pin "12") (pinfunction "12_12") (pintype "passive"))
    )
    (net (code "45") (name "D02MEM11") (class "Default")
      (node (ref "E20") (pin "5") (pinfunction "O_5") (pintype "open_collector"))
      (node (ref "H05/H24") (pin "16") (pinfunction "16_16") (pintype "passive"))
    )
    (net (code "46") (name "D03BEMA0L") (class "Default")
      (node (ref "E6") (pin "6") (pinfunction "~{Q}_6") (pintype "output"))
      (node (ref "U$1") (pin "AD2") (pinfunction "1_AD2") (pintype "bidirectional"))
    )
    (net (code "47") (name "D03BEMA1L") (class "Default")
      (node (ref "E6") (pin "8") (pinfunction "~{Q}_8") (pintype "output"))
      (node (ref "U$1") (pin "AE2") (pinfunction "1_AE2") (pintype "bidirectional"))
    )
    (net (code "48") (name "D03BEMA2L") (class "Default")
      (node (ref "E9") (pin "8") (pinfunction "~{Q}_8") (pintype "output"))
      (node (ref "U$1") (pin "AH2") (pinfunction "1_AH2") (pintype "bidirectional"))
    )
    (net (code "49") (name "D03BMA0") (class "Default")
      (node (ref "E1") (pin "11") (pinfunction "A1_11") (pintype "input"))
      (node (ref "H01/H20") (pin "16") (pinfunction "16_16") (pintype "passive"))
    )
    (net (code "50") (name "D03BMA1") (class "Default")
      (node (ref "E1") (pin "13") (pinfunction "A2_13") (pintype "input"))
      (node (ref "H01/H20") (pin "20") (pinfunction "20_20") (pintype "passive"))
    )
    (net (code "51") (name "D03BMA2") (class "Default")
      (node (ref "E1") (pin "15") (pinfunction "A3_15") (pintype "input"))
      (node (ref "H01/H20") (pin "24") (pinfunction "24_24") (pintype "passive"))
    )
    (net (code "52") (name "D03BMA3") (class "Default")
      (node (ref "E1") (pin "17") (pinfunction "A4_17") (pintype "input"))
      (node (ref "H01/H20") (pin "28") (pinfunction "28_28") (pintype "passive"))
    )
    (net (code "53") (name "D03BMA4") (class "Default")
      (node (ref "E14") (pin "2") (pinfunction "A1_2") (pintype "input"))
      (node (ref "H01/H20") (pin "30") (pinfunction "30_30") (pintype "passive"))
    )
    (net (code "54") (name "D03BMA5") (class "Default")
      (node (ref "E14") (pin "4") (pinfunction "A2_4") (pintype "input"))
      (node (ref "H01/H20") (pin "32") (pinfunction "32_32") (pintype "passive"))
    )
    (net (code "55") (name "D03BMA6") (class "Default")
      (node (ref "E14") (pin "6") (pinfunction "A3_6") (pintype "input"))
      (node (ref "H02/H21") (pin "6") (pinfunction "6_6") (pintype "passive"))
    )
    (net (code "56") (name "D03BMA7") (class "Default")
      (node (ref "E14") (pin "8") (pinfunction "A4_8") (pintype "input"))
      (node (ref "H02/H21") (pin "8") (pinfunction "8_8") (pintype "passive"))
    )
    (net (code "57") (name "D03BMA8") (class "Default")
      (node (ref "E38") (pin "2") (pinfunction "A1_2") (pintype "input"))
      (node (ref "H02/H21") (pin "12") (pinfunction "12_12") (pintype "passive"))
    )
    (net (code "58") (name "D03BMA9") (class "Default")
      (node (ref "E38") (pin "4") (pinfunction "A2_4") (pintype "input"))
      (node (ref "H02/H21") (pin "16") (pinfunction "16_16") (pintype "passive"))
    )
    (net (code "59") (name "D03BMA10") (class "Default")
      (node (ref "E38") (pin "6") (pinfunction "A3_6") (pintype "input"))
      (node (ref "H02/H21") (pin "20") (pinfunction "20_20") (pintype "passive"))
    )
    (net (code "60") (name "D03BMA11") (class "Default")
      (node (ref "E38") (pin "8") (pinfunction "A4_8") (pintype "input"))
      (node (ref "H02/H21") (pin "24") (pinfunction "24_24") (pintype "passive"))
    )
    (net (code "61") (name "D03BTP2") (class "Default")
      (node (ref "E12") (pin "11") (pinfunction "CLK_11") (pintype "input"))
      (node (ref "E15") (pin "1") (pinfunction "I_1") (pintype "input"))
      (node (ref "H05/H24") (pin "32") (pinfunction "32_32") (pintype "passive"))
    )
    (net (code "62") (name "D03EA0") (class "Default")
      (node (ref "E1") (pin "2") (pinfunction "A1_2") (pintype "input"))
      (node (ref "H03/H22") (pin "6") (pinfunction "6_6") (pintype "passive"))
    )
    (net (code "63") (name "D03EA1") (class "Default")
      (node (ref "E1") (pin "4") (pinfunction "A2_4") (pintype "input"))
      (node (ref "H03/H22") (pin "8") (pinfunction "8_8") (pintype "passive"))
    )
    (net (code "64") (name "D03EA2") (class "Default")
      (node (ref "E1") (pin "6") (pinfunction "A3_6") (pintype "input"))
      (node (ref "H03/H22") (pin "12") (pinfunction "12_12") (pintype "passive"))
    )
    (net (code "65") (name "D03EMA0H") (class "Default")
      (node (ref "E6") (pin "2") (pinfunction "D_2") (pintype "input"))
      (node (ref "E7") (pin "8") (pinfunction "O_8") (pintype "output"))
      (node (ref "E8") (pin "9") (pinfunction "I0_9") (pintype "input"))
      (node (ref "JP1") (pin "1") (pinfunction "1_1") (pintype "passive"))
    )
    (net (code "66") (name "D03EMA0L") (class "Default")
      (node (ref "E1") (pin "18") (pinfunction "Y1_18") (pintype "tri_state"))
      (node (ref "E7") (pin "1") (pinfunction "I_1") (pintype "input"))
      (node (ref "E7") (pin "9") (pinfunction "I_9") (pintype "input"))
      (node (ref "E8") (pin "4") (pinfunction "I0_4") (pintype "input"))
      (node (ref "JP1") (pin "3") (pinfunction "3_3") (pintype "passive"))
    )
    (net (code "67") (name "D03EMA1H") (class "Default")
      (node (ref "E6") (pin "12") (pinfunction "D_12") (pintype "input"))
      (node (ref "E7") (pin "10") (pinfunction "O_10") (pintype "output"))
      (node (ref "E8") (pin "10") (pinfunction "I1_10") (pintype "input"))
      (node (ref "JP2") (pin "3") (pinfunction "3_3") (pintype "passive"))
    )
    (net (code "68") (name "D03EMA1L") (class "Default")
      (node (ref "E1") (pin "16") (pinfunction "Y2_16") (pintype "tri_state"))
      (node (ref "E7") (pin "11") (pinfunction "I_11") (pintype "input"))
      (node (ref "E8") (pin "5") (pinfunction "I1_5") (pintype "input"))
      (node (ref "JP2") (pin "1") (pinfunction "1_1") (pintype "passive"))
    )
    (net (code "69") (name "D03EMA2H") (class "Default")
      (node (ref "E7") (pin "12") (pinfunction "O_12") (pintype "output"))
      (node (ref "E9") (pin "12") (pinfunction "D_12") (pintype "input"))
      (node (ref "JP3") (pin "1") (pinfunction "1_1") (pintype "passive"))
    )
    (net (code "70") (name "D03EMA2L") (class "Default")
      (node (ref "E1") (pin "14") (pinfunction "Y3_14") (pintype "tri_state"))
      (node (ref "E7") (pin "13") (pinfunction "I_13") (pintype "input"))
      (node (ref "JP3") (pin "3") (pinfunction "3_3") (pintype "passive"))
    )
    (net (code "71") (name "D03MA0L") (class "Default")
      (node (ref "E1") (pin "9") (pinfunction "Y1_9") (pintype "tri_state"))
      (node (ref "U$1") (pin "AD1") (pinfunction "1_AD1") (pintype "bidirectional"))
    )
    (net (code "72") (name "D03MA1L") (class "Default")
      (node (ref "E1") (pin "7") (pinfunction "Y2_7") (pintype "tri_state"))
      (node (ref "U$1") (pin "AE1") (pinfunction "1_AE1") (pintype "bidirectional"))
    )
    (net (code "73") (name "D03MA2L") (class "Default")
      (node (ref "E1") (pin "5") (pinfunction "Y3_5") (pintype "tri_state"))
      (node (ref "U$1") (pin "AH1") (pinfunction "1_AH1") (pintype "bidirectional"))
    )
    (net (code "74") (name "D03MA3L") (class "Default")
      (node (ref "E1") (pin "3") (pinfunction "Y4_3") (pintype "tri_state"))
      (node (ref "U$1") (pin "AJ1") (pinfunction "1_AJ1") (pintype "bidirectional"))
    )
    (net (code "75") (name "D03MA4L") (class "Default")
      (node (ref "E14") (pin "18") (pinfunction "Y1_18") (pintype "tri_state"))
      (node (ref "U$1") (pin "BD1") (pinfunction "1_BD1") (pintype "bidirectional"))
    )
    (net (code "76") (name "D03MA5L") (class "Default")
      (node (ref "E14") (pin "16") (pinfunction "Y2_16") (pintype "tri_state"))
      (node (ref "U$1") (pin "BE1") (pinfunction "1_BE1") (pintype "bidirectional"))
    )
    (net (code "77") (name "D03MA6L") (class "Default")
      (node (ref "E14") (pin "14") (pinfunction "Y3_14") (pintype "tri_state"))
      (node (ref "U$1") (pin "BH1") (pinfunction "1_BH1") (pintype "bidirectional"))
    )
    (net (code "78") (name "D03MA7L") (class "Default")
      (node (ref "E14") (pin "12") (pinfunction "Y4_12") (pintype "tri_state"))
      (node (ref "U$1") (pin "BJ1") (pinfunction "1_BJ1") (pintype "bidirectional"))
    )
    (net (code "79") (name "D03MA8L") (class "Default")
      (node (ref "E38") (pin "18") (pinfunction "Y1_18") (pintype "tri_state"))
      (node (ref "U$1") (pin "DD1") (pinfunction "1_DD1") (pintype "bidirectional"))
    )
    (net (code "80") (name "D03MA9L") (class "Default")
      (node (ref "E38") (pin "16") (pinfunction "Y2_16") (pintype "tri_state"))
      (node (ref "U$1") (pin "DE1") (pinfunction "1_DE1") (pintype "bidirectional"))
    )
    (net (code "81") (name "D03MA10L") (class "Default")
      (node (ref "E38") (pin "14") (pinfunction "Y3_14") (pintype "tri_state"))
      (node (ref "U$1") (pin "DH1") (pinfunction "1_DH1") (pintype "bidirectional"))
    )
    (net (code "82") (name "D03MA11L") (class "Default")
      (node (ref "E38") (pin "12") (pinfunction "Y4_12") (pintype "tri_state"))
      (node (ref "U$1") (pin "DJ1") (pinfunction "1_DJ1") (pintype "bidirectional"))
    )
    (net (code "83") (name "D03MCBMB0L") (class "Default")
      (node (ref "E37") (pin "1") (pinfunction "I0_1") (pintype "input"))
      (node (ref "H02/H21") (pin "28") (pinfunction "28_28") (pintype "passive"))
    )
    (net (code "84") (name "D03MCBMB1L") (class "Default")
      (node (ref "E37") (pin "6") (pinfunction "I0_6") (pintype "input"))
      (node (ref "H02/H21") (pin "30") (pinfunction "30_30") (pintype "passive"))
    )
    (net (code "85") (name "D03MCBMB2L") (class "Default")
      (node (ref "E41") (pin "6") (pinfunction "I0_6") (pintype "input"))
      (node (ref "H02/H21") (pin "32") (pinfunction "32_32") (pintype "passive"))
    )
    (net (code "86") (name "D03MCBMB3L") (class "Default")
      (node (ref "E40") (pin "1") (pinfunction "I0_1") (pintype "input"))
      (node (ref "H01/H20") (pin "6") (pinfunction "6_6") (pintype "passive"))
    )
    (net (code "87") (name "D03MCBMB4L") (class "Default")
      (node (ref "E40") (pin "6") (pinfunction "I0_6") (pintype "input"))
      (node (ref "H01/H20") (pin "8") (pinfunction "8_8") (pintype "passive"))
    )
    (net (code "88") (name "D03MCBMB5L") (class "Default")
      (node (ref "E41") (pin "1") (pinfunction "I0_1") (pintype "input"))
      (node (ref "H01/H20") (pin "12") (pinfunction "12_12") (pintype "passive"))
    )
    (net (code "89") (name "D03MCBMB6L") (class "Default")
      (node (ref "E36") (pin "1") (pinfunction "I0_1") (pintype "input"))
      (node (ref "H03/H22") (pin "16") (pinfunction "16_16") (pintype "passive"))
    )
    (net (code "90") (name "D03MCBMB7L") (class "Default")
      (node (ref "E36") (pin "6") (pinfunction "I0_6") (pintype "input"))
      (node (ref "H03/H22") (pin "20") (pinfunction "20_20") (pintype "passive"))
    )
    (net (code "91") (name "D03MCBMB8L") (class "Default")
      (node (ref "E33") (pin "1") (pinfunction "I0_1") (pintype "input"))
      (node (ref "H03/H22") (pin "24") (pinfunction "24_24") (pintype "passive"))
    )
    (net (code "92") (name "D03MCBMB9L") (class "Default")
      (node (ref "E33") (pin "6") (pinfunction "I0_6") (pintype "input"))
      (node (ref "H03/H22") (pin "28") (pinfunction "28_28") (pintype "passive"))
    )
    (net (code "93") (name "D03MCBMB10L") (class "Default")
      (node (ref "E34") (pin "1") (pinfunction "I0_1") (pintype "input"))
      (node (ref "H03/H22") (pin "30") (pinfunction "30_30") (pintype "passive"))
    )
    (net (code "94") (name "D03MCBMB11L") (class "Default")
      (node (ref "E34") (pin "6") (pinfunction "I0_6") (pintype "input"))
      (node (ref "H03/H22") (pin "32") (pinfunction "32_32") (pintype "passive"))
    )
    (net (code "95") (name "D03MEMSTART") (class "Default")
      (node (ref "E12") (pin "3") (pinfunction "CLK_3") (pintype "input"))
      (node (ref "E15") (pin "5") (pinfunction "I_5") (pintype "input"))
      (node (ref "E6") (pin "11") (pinfunction "CLK_11") (pintype "input"))
      (node (ref "E6") (pin "3") (pinfunction "CLK_3") (pintype "input"))
      (node (ref "E9") (pin "11") (pinfunction "CLK_11") (pintype "input"))
      (node (ref "H05/H24") (pin "20") (pinfunction "20_20") (pintype "passive"))
    )
    (net (code "96") (name "D04MD0L") (class "Default")
      (node (ref "E2") (pin "12") (pinfunction "D_12") (pintype "input"))
      (node (ref "E37") (pin "3") (pinfunction "O_3") (pintype "open_collector"))
      (node (ref "U$1") (pin "AK1") (pinfunction "1_AK1") (pintype "bidirectional"))
    )
    (net (code "97") (name "D04MD1L") (class "Default")
      (node (ref "E2") (pin "2") (pinfunction "D_2") (pintype "input"))
      (node (ref "E37") (pin "5") (pinfunction "O_5") (pintype "open_collector"))
      (node (ref "U$1") (pin "AL1") (pinfunction "1_AL1") (pintype "bidirectional"))
    )
    (net (code "98") (name "D04MD2L") (class "Default")
      (node (ref "E41") (pin "5") (pinfunction "O_5") (pintype "open_collector"))
      (node (ref "E5") (pin "12") (pinfunction "D_12") (pintype "input"))
      (node (ref "U$1") (pin "AM1") (pinfunction "1_AM1") (pintype "bidirectional"))
    )
    (net (code "99") (name "D04MD3L") (class "Default")
      (node (ref "E40") (pin "3") (pinfunction "O_3") (pintype "open_collector"))
      (node (ref "E5") (pin "2") (pinfunction "D_2") (pintype "input"))
      (node (ref "U$1") (pin "AP1") (pinfunction "1_AP1") (pintype "bidirectional"))
    )
    (net (code "100") (name "D04MD4L") (class "Default")
      (node (ref "E17") (pin "12") (pinfunction "D_12") (pintype "input"))
      (node (ref "E40") (pin "5") (pinfunction "O_5") (pintype "open_collector"))
      (node (ref "U$1") (pin "BK1") (pinfunction "1_BK1") (pintype "bidirectional"))
    )
    (net (code "101") (name "D04MD5L") (class "Default")
      (node (ref "E17") (pin "2") (pinfunction "D_2") (pintype "input"))
      (node (ref "E41") (pin "3") (pinfunction "O_3") (pintype "open_collector"))
      (node (ref "U$1") (pin "BL1") (pinfunction "1_BL1") (pintype "bidirectional"))
    )
    (net (code "102") (name "D04MD6L") (class "Default")
      (node (ref "E18") (pin "12") (pinfunction "D_12") (pintype "input"))
      (node (ref "E36") (pin "3") (pinfunction "O_3") (pintype "open_collector"))
      (node (ref "U$1") (pin "BM1") (pinfunction "1_BM1") (pintype "bidirectional"))
    )
    (net (code "103") (name "D04MD7L") (class "Default")
      (node (ref "E18") (pin "2") (pinfunction "D_2") (pintype "input"))
      (node (ref "E36") (pin "5") (pinfunction "O_5") (pintype "open_collector"))
      (node (ref "U$1") (pin "BP1") (pinfunction "1_BP1") (pintype "bidirectional"))
    )
    (net (code "104") (name "D04MD8L") (class "Default")
      (node (ref "E33") (pin "3") (pinfunction "O_3") (pintype "open_collector"))
      (node (ref "E43") (pin "12") (pinfunction "D_12") (pintype "input"))
      (node (ref "U$1") (pin "DK1") (pinfunction "1_DK1") (pintype "bidirectional"))
    )
    (net (code "105") (name "D04MD9L") (class "Default")
      (node (ref "E33") (pin "5") (pinfunction "O_5") (pintype "open_collector"))
      (node (ref "E43") (pin "2") (pinfunction "D_2") (pintype "input"))
      (node (ref "U$1") (pin "DL1") (pinfunction "1_DL1") (pintype "bidirectional"))
    )
    (net (code "106") (name "D04MD10L") (class "Default")
      (node (ref "E34") (pin "3") (pinfunction "O_3") (pintype "open_collector"))
      (node (ref "E42") (pin "12") (pinfunction "D_12") (pintype "input"))
      (node (ref "U$1") (pin "DM1") (pinfunction "1_DM1") (pintype "bidirectional"))
    )
    (net (code "107") (name "D04MD11L") (class "Default")
      (node (ref "E34") (pin "5") (pinfunction "O_5") (pintype "open_collector"))
      (node (ref "E42") (pin "2") (pinfunction "D_2") (pintype "input"))
      (node (ref "U$1") (pin "DP1") (pinfunction "1_DP1") (pintype "bidirectional"))
    )
    (net (code "108") (name "GND") (class "Default")
      (node (ref "C10") (pin "2") (pinfunction "2_2") (pintype "passive"))
      (node (ref "C11") (pin "2") (pinfunction "2_2") (pintype "passive"))
      (node (ref "C12") (pin "2") (pinfunction "2_2") (pintype "passive"))
      (node (ref "C13") (pin "2") (pinfunction "2_2") (pintype "passive"))
      (node (ref "C14") (pin "2") (pinfunction "2_2") (pintype "passive"))
      (node (ref "C15") (pin "2") (pinfunction "2_2") (pintype "passive"))
      (node (ref "C16") (pin "2") (pinfunction "2_2") (pintype "passive"))
      (node (ref "C17") (pin "2") (pinfunction "2_2") (pintype "passive"))
      (node (ref "C18") (pin "2") (pinfunction "2_2") (pintype "passive"))
      (node (ref "C19") (pin "2") (pinfunction "2_2") (pintype "passive"))
      (node (ref "C20") (pin "2") (pinfunction "2_2") (pintype "passive"))
      (node (ref "C21") (pin "2") (pinfunction "2_2") (pintype "passive"))
      (node (ref "C22") (pin "2") (pinfunction "2_2") (pintype "passive"))
      (node (ref "C23") (pin "2") (pinfunction "2_2") (pintype "passive"))
      (node (ref "C24") (pin "2") (pinfunction "2_2") (pintype "passive"))
      (node (ref "C25") (pin "2") (pinfunction "2_2") (pintype "passive"))
      (node (ref "C26") (pin "2") (pinfunction "2_2") (pintype "passive"))
      (node (ref "C27") (pin "2") (pinfunction "2_2") (pintype "passive"))
      (node (ref "C28") (pin "2") (pinfunction "2_2") (pintype "passive"))
      (node (ref "C29") (pin "2") (pinfunction "2_2") (pintype "passive"))
      (node (ref "C30") (pin "2") (pinfunction "2_2") (pintype "passive"))
      (node (ref "C31") (pin "2") (pinfunction "2_2") (pintype "passive"))
      (node (ref "C32") (pin "2") (pinfunction "2_2") (pintype "passive"))
      (node (ref "C33") (pin "2") (pinfunction "2_2") (pintype "passive"))
      (node (ref "C34") (pin "2") (pinfunction "2_2") (pintype "passive"))
      (node (ref "C35") (pin "2") (pinfunction "2_2") (pintype "passive"))
      (node (ref "C36") (pin "2") (pinfunction "2_2") (pintype "passive"))
      (node (ref "C37") (pin "2") (pinfunction "2_2") (pintype "passive"))
      (node (ref "C38") (pin "2") (pinfunction "2_2") (pintype "passive"))
      (node (ref "C39") (pin "2") (pinfunction "2_2") (pintype "passive"))
      (node (ref "C40") (pin "2") (pinfunction "2_2") (pintype "passive"))
      (node (ref "C41") (pin "2") (pinfunction "2_2") (pintype "passive"))
      (node (ref "C42") (pin "2") (pinfunction "2_2") (pintype "passive"))
      (node (ref "C43") (pin "2") (pinfunction "2_2") (pintype "passive"))
      (node (ref "C44") (pin "2") (pinfunction "2_2") (pintype "passive"))
      (node (ref "C45") (pin "2") (pinfunction "2_2") (pintype "passive"))
      (node (ref "C46") (pin "2") (pinfunction "2_2") (pintype "passive"))
      (node (ref "C47") (pin "2") (pinfunction "2_2") (pintype "passive"))
      (node (ref "C48") (pin "2") (pinfunction "2_2") (pintype "passive"))
      (node (ref "C49") (pin "-") (pinfunction "-_-") (pintype "passive"))
      (node (ref "C50") (pin "-") (pinfunction "-_-") (pintype "passive"))
      (node (ref "C51") (pin "-") (pinfunction "-_-") (pintype "passive"))
      (node (ref "C52") (pin "-") (pinfunction "-_-") (pintype "passive"))
      (node (ref "C6") (pin "2") (pinfunction "2_2") (pintype "passive"))
      (node (ref "C7") (pin "2") (pinfunction "2_2") (pintype "passive"))
      (node (ref "C8") (pin "2") (pinfunction "2_2") (pintype "passive"))
      (node (ref "C9") (pin "2") (pinfunction "2_2") (pintype "passive"))
      (node (ref "D1") (pin "A") (pinfunction "A_A") (pintype "passive"))
      (node (ref "D2") (pin "A") (pinfunction "A_A") (pintype "passive"))
      (node (ref "D3") (pin "A") (pinfunction "A_A") (pintype "passive"))
      (node (ref "D4") (pin "A") (pinfunction "A_A") (pintype "passive"))
      (node (ref "D5") (pin "A") (pinfunction "A_A") (pintype "passive"))
      (node (ref "E1") (pin "1") (pinfunction "G_1") (pintype "input"))
      (node (ref "E1") (pin "19") (pinfunction "G_19") (pintype "input"))
      (node (ref "E1") (pin "8") (pinfunction "A4_8") (pintype "input"))
      (node (ref "E10") (pin "12") (pinfunction "D_12") (pintype "input"))
      (node (ref "E10") (pin "2") (pinfunction "D_2") (pintype "input"))
      (node (ref "E12") (pin "12") (pinfunction "D_12") (pintype "input"))
      (node (ref "E13") (pin "12") (pinfunction "D_12") (pintype "input"))
      (node (ref "E13") (pin "2") (pinfunction "D_2") (pintype "input"))
      (node (ref "E14") (pin "1") (pinfunction "G_1") (pintype "input"))
      (node (ref "E14") (pin "17") (pinfunction "A4_17") (pintype "input"))
      (node (ref "E14") (pin "19") (pinfunction "G_19") (pintype "input"))
      (node (ref "E24") (pin "1") (pinfunction "G_1") (pintype "input"))
      (node (ref "E24") (pin "15") (pinfunction "A3_15") (pintype "input"))
      (node (ref "E24") (pin "17") (pinfunction "A4_17") (pintype "input"))
      (node (ref "E24") (pin "19") (pinfunction "G_19") (pintype "input"))
      (node (ref "E24") (pin "8") (pinfunction "A4_8") (pintype "input"))
      (node (ref "E38") (pin "1") (pinfunction "G_1") (pintype "input"))
      (node (ref "E4") (pin "1") (pinfunction "G_1") (pintype "input"))
      (node (ref "E4") (pin "19") (pinfunction "G_19") (pintype "input"))
      (node (ref "E4") (pin "6") (pinfunction "A3_6") (pintype "input"))
      (node (ref "E4") (pin "8") (pinfunction "A4_8") (pintype "input"))
      (node (ref "E8") (pin "1") (pinfunction "I0_1") (pintype "input"))
      (node (ref "E8") (pin "2") (pinfunction "I1_2") (pintype "input"))
      (node (ref "E9") (pin "2") (pinfunction "D_2") (pintype "input"))
      (node (ref "H01/H20") (pin "1") (pinfunction "1_1") (pintype "passive"))
      (node (ref "H01/H20") (pin "11") (pinfunction "11_11") (pintype "passive"))
      (node (ref "H01/H20") (pin "13") (pinfunction "13_13") (pintype "passive"))
      (node (ref "H01/H20") (pin "15") (pinfunction "15_15") (pintype "passive"))
      (node (ref "H01/H20") (pin "17") (pinfunction "17_17") (pintype "passive"))
      (node (ref "H01/H20") (pin "19") (pinfunction "19_19") (pintype "passive"))
      (node (ref "H01/H20") (pin "21") (pinfunction "21_21") (pintype "passive"))
      (node (ref "H01/H20") (pin "23") (pinfunction "23_23") (pintype "passive"))
      (node (ref "H01/H20") (pin "25") (pinfunction "25_25") (pintype "passive"))
      (node (ref "H01/H20") (pin "27") (pinfunction "27_27") (pintype "passive"))
      (node (ref "H01/H20") (pin "29") (pinfunction "29_29") (pintype "passive"))
      (node (ref "H01/H20") (pin "3") (pinfunction "3_3") (pintype "passive"))
      (node (ref "H01/H20") (pin "31") (pinfunction "31_31") (pintype "passive"))
      (node (ref "H01/H20") (pin "33") (pinfunction "33_33") (pintype "passive"))
      (node (ref "H01/H20") (pin "5") (pinfunction "5_5") (pintype "passive"))
      (node (ref "H01/H20") (pin "7") (pinfunction "7_7") (pintype "passive"))
      (node (ref "H01/H20") (pin "9") (pinfunction "9_9") (pintype "passive"))
      (node (ref "H02/H21") (pin "1") (pinfunction "1_1") (pintype "passive"))
      (node (ref "H02/H21") (pin "11") (pinfunction "11_11") (pintype "passive"))
      (node (ref "H02/H21") (pin "13") (pinfunction "13_13") (pintype "passive"))
      (node (ref "H02/H21") (pin "15") (pinfunction "15_15") (pintype "passive"))
      (node (ref "H02/H21") (pin "17") (pinfunction "17_17") (pintype "passive"))
      (node (ref "H02/H21") (pin "19") (pinfunction "19_19") (pintype "passive"))
      (node (ref "H02/H21") (pin "21") (pinfunction "21_21") (pintype "passive"))
      (node (ref "H02/H21") (pin "23") (pinfunction "23_23") (pintype "passive"))
      (node (ref "H02/H21") (pin "25") (pinfunction "25_25") (pintype "passive"))
      (node (ref "H02/H21") (pin "27") (pinfunction "27_27") (pintype "passive"))
      (node (ref "H02/H21") (pin "29") (pinfunction "29_29") (pintype "passive"))
      (node (ref "H02/H21") (pin "3") (pinfunction "3_3") (pintype "passive"))
      (node (ref "H02/H21") (pin "31") (pinfunction "31_31") (pintype "passive"))
      (node (ref "H02/H21") (pin "33") (pinfunction "33_33") (pintype "passive"))
      (node (ref "H02/H21") (pin "5") (pinfunction "5_5") (pintype "passive"))
      (node (ref "H02/H21") (pin "7") (pinfunction "7_7") (pintype "passive"))
      (node (ref "H02/H21") (pin "9") (pinfunction "9_9") (pintype "passive"))
      (node (ref "H03/H22") (pin "1") (pinfunction "1_1") (pintype "passive"))
      (node (ref "H03/H22") (pin "11") (pinfunction "11_11") (pintype "passive"))
      (node (ref "H03/H22") (pin "13") (pinfunction "13_13") (pintype "passive"))
      (node (ref "H03/H22") (pin "15") (pinfunction "15_15") (pintype "passive"))
      (node (ref "H03/H22") (pin "17") (pinfunction "17_17") (pintype "passive"))
      (node (ref "H03/H22") (pin "19") (pinfunction "19_19") (pintype "passive"))
      (node (ref "H03/H22") (pin "21") (pinfunction "21_21") (pintype "passive"))
      (node (ref "H03/H22") (pin "23") (pinfunction "23_23") (pintype "passive"))
      (node (ref "H03/H22") (pin "25") (pinfunction "25_25") (pintype "passive"))
      (node (ref "H03/H22") (pin "27") (pinfunction "27_27") (pintype "passive"))
      (node (ref "H03/H22") (pin "29") (pinfunction "29_29") (pintype "passive"))
      (node (ref "H03/H22") (pin "3") (pinfunction "3_3") (pintype "passive"))
      (node (ref "H03/H22") (pin "31") (pinfunction "31_31") (pintype "passive"))
      (node (ref "H03/H22") (pin "33") (pinfunction "33_33") (pintype "passive"))
      (node (ref "H03/H22") (pin "5") (pinfunction "5_5") (pintype "passive"))
      (node (ref "H03/H22") (pin "7") (pinfunction "7_7") (pintype "passive"))
      (node (ref "H03/H22") (pin "9") (pinfunction "9_9") (pintype "passive"))
      (node (ref "H04/H23") (pin "1") (pinfunction "1_1") (pintype "passive"))
      (node (ref "H04/H23") (pin "11") (pinfunction "11_11") (pintype "passive"))
      (node (ref "H04/H23") (pin "13") (pinfunction "13_13") (pintype "passive"))
      (node (ref "H04/H23") (pin "15") (pinfunction "15_15") (pintype "passive"))
      (node (ref "H04/H23") (pin "17") (pinfunction "17_17") (pintype "passive"))
      (node (ref "H04/H23") (pin "19") (pinfunction "19_19") (pintype "passive"))
      (node (ref "H04/H23") (pin "21") (pinfunction "21_21") (pintype "passive"))
      (node (ref "H04/H23") (pin "23") (pinfunction "23_23") (pintype "passive"))
      (node (ref "H04/H23") (pin "25") (pinfunction "25_25") (pintype "passive"))
      (node (ref "H04/H23") (pin "27") (pinfunction "27_27") (pintype "passive"))
      (node (ref "H04/H23") (pin "29") (pinfunction "29_29") (pintype "passive"))
      (node (ref "H04/H23") (pin "3") (pinfunction "3_3") (pintype "passive"))
      (node (ref "H04/H23") (pin "31") (pinfunction "31_31") (pintype "passive"))
      (node (ref "H04/H23") (pin "33") (pinfunction "33_33") (pintype "passive"))
      (node (ref "H04/H23") (pin "5") (pinfunction "5_5") (pintype "passive"))
      (node (ref "H04/H23") (pin "7") (pinfunction "7_7") (pintype "passive"))
      (node (ref "H04/H23") (pin "9") (pinfunction "9_9") (pintype "passive"))
      (node (ref "H05/H24") (pin "1") (pinfunction "1_1") (pintype "passive"))
      (node (ref "H05/H24") (pin "11") (pinfunction "11_11") (pintype "passive"))
      (node (ref "H05/H24") (pin "13") (pinfunction "13_13") (pintype "passive"))
      (node (ref "H05/H24") (pin "15") (pinfunction "15_15") (pintype "passive"))
      (node (ref "H05/H24") (pin "17") (pinfunction "17_17") (pintype "passive"))
      (node (ref "H05/H24") (pin "19") (pinfunction "19_19") (pintype "passive"))
      (node (ref "H05/H24") (pin "21") (pinfunction "21_21") (pintype "passive"))
      (node (ref "H05/H24") (pin "23") (pinfunction "23_23") (pintype "passive"))
      (node (ref "H05/H24") (pin "25") (pinfunction "25_25") (pintype "passive"))
      (node (ref "H05/H24") (pin "27") (pinfunction "27_27") (pintype "passive"))
      (node (ref "H05/H24") (pin "29") (pinfunction "29_29") (pintype "passive"))
      (node (ref "H05/H24") (pin "3") (pinfunction "3_3") (pintype "passive"))
      (node (ref "H05/H24") (pin "31") (pinfunction "31_31") (pintype "passive"))
      (node (ref "H05/H24") (pin "33") (pinfunction "33_33") (pintype "passive"))
      (node (ref "H05/H24") (pin "5") (pinfunction "5_5") (pintype "passive"))
      (node (ref "H05/H24") (pin "7") (pinfunction "7_7") (pintype "passive"))
      (node (ref "H05/H24") (pin "9") (pinfunction "9_9") (pintype "passive"))
      (node (ref "JP2") (pin "5") (pinfunction "5_5") (pintype "passive"))
      (node (ref "R12") (pin "2") (pinfunction "2_2") (pintype "passive"))
      (node (ref "R16") (pin "2") (pinfunction "2_2") (pintype "passive"))
      (node (ref "R18") (pin "2") (pinfunction "2_2") (pintype "passive"))
      (node (ref "R19") (pin "1") (pinfunction "1_1") (pintype "passive"))
      (node (ref "R21") (pin "1") (pinfunction "1_1") (pintype "passive"))
      (node (ref "R25") (pin "1") (pinfunction "1_1") (pintype "passive"))
      (node (ref "R27") (pin "1") (pinfunction "1_1") (pintype "passive"))
      (node (ref "R29") (pin "1") (pinfunction "1_1") (pintype "passive"))
      (node (ref "U$1") (pin "AC1") (pinfunction "1_AC1") (pintype "bidirectional"))
      (node (ref "U$1") (pin "AC2") (pinfunction "1_AC2") (pintype "bidirectional"))
      (node (ref "U$1") (pin "AF1") (pinfunction "1_AF1") (pintype "bidirectional"))
      (node (ref "U$1") (pin "AF2") (pinfunction "1_AF2") (pintype "bidirectional"))
      (node (ref "U$1") (pin "AN1") (pinfunction "1_AN1") (pintype "bidirectional"))
      (node (ref "U$1") (pin "AN2") (pinfunction "1_AN2") (pintype "bidirectional"))
      (node (ref "U$1") (pin "AT1") (pinfunction "1_AT1") (pintype "bidirectional"))
      (node (ref "U$1") (pin "AT2") (pinfunction "1_AT2") (pintype "bidirectional"))
      (node (ref "U$1") (pin "BC1") (pinfunction "1_BC1") (pintype "bidirectional"))
      (node (ref "U$1") (pin "BC2") (pinfunction "1_BC2") (pintype "bidirectional"))
      (node (ref "U$1") (pin "BF1") (pinfunction "1_BF1") (pintype "bidirectional"))
      (node (ref "U$1") (pin "BF2") (pinfunction "1_BF2") (pintype "bidirectional"))
      (node (ref "U$1") (pin "BN1") (pinfunction "1_BN1") (pintype "bidirectional"))
      (node (ref "U$1") (pin "BN2") (pinfunction "1_BN2") (pintype "bidirectional"))
      (node (ref "U$1") (pin "BT1") (pinfunction "1_BT1") (pintype "bidirectional"))
      (node (ref "U$1") (pin "BT2") (pinfunction "1_BT2") (pintype "bidirectional"))
      (node (ref "U$1") (pin "CC1") (pinfunction "1_CC1") (pintype "bidirectional"))
      (node (ref "U$1") (pin "CC2") (pinfunction "1_CC2") (pintype "bidirectional"))
      (node (ref "U$1") (pin "CF1") (pinfunction "1_CF1") (pintype "bidirectional"))
      (node (ref "U$1") (pin "CF2") (pinfunction "1_CF2") (pintype "bidirectional"))
      (node (ref "U$1") (pin "CN1") (pinfunction "1_CN1") (pintype "bidirectional"))
      (node (ref "U$1") (pin "CN2") (pinfunction "1_CN2") (pintype "bidirectional"))
      (node (ref "U$1") (pin "CT1") (pinfunction "1_CT1") (pintype "bidirectional"))
      (node (ref "U$1") (pin "CT2") (pinfunction "1_CT2") (pintype "bidirectional"))
      (node (ref "U$1") (pin "DC1") (pinfunction "1_DC1") (pintype "bidirectional"))
      (node (ref "U$1") (pin "DC2") (pinfunction "1_DC2") (pintype "bidirectional"))
      (node (ref "U$1") (pin "DF1") (pinfunction "1_DF1") (pintype "bidirectional"))
      (node (ref "U$1") (pin "DF2") (pinfunction "1_DF2") (pintype "bidirectional"))
      (node (ref "U$1") (pin "DN1") (pinfunction "1_DN1") (pintype "bidirectional"))
      (node (ref "U$1") (pin "DN2") (pinfunction "1_DN2") (pintype "bidirectional"))
      (node (ref "U$1") (pin "DT1") (pinfunction "1_DT1") (pintype "bidirectional"))
      (node (ref "U$1") (pin "DT2") (pinfunction "1_DT2") (pintype "bidirectional"))
    )
    (net (code "109") (name "Net-(E2A-CLK)") (class "Default")
      (node (ref "E2") (pin "11") (pinfunction "CLK_11") (pintype "input"))
      (node (ref "E2") (pin "3") (pinfunction "CLK_3") (pintype "input"))
      (node (ref "E39") (pin "3") (pinfunction "O_3") (pintype "output"))
      (node (ref "E5") (pin "11") (pinfunction "CLK_11") (pintype "input"))
      (node (ref "E5") (pin "3") (pinfunction "CLK_3") (pintype "input"))
    )
    (net (code "110") (name "Net-(E4A-A2)") (class "Default")
      (node (ref "E4") (pin "4") (pinfunction "A2_4") (pintype "input"))
      (node (ref "E9") (pin "6") (pinfunction "~{Q}_6") (pintype "output"))
    )
    (net (code "111") (name "Net-(E7A-O)") (class "Default")
      (node (ref "E7") (pin "2") (pinfunction "O_2") (pintype "output"))
      (node (ref "JP4") (pin "3") (pinfunction "3_3") (pintype "passive"))
    )
    (net (code "112") (name "Net-(E7B-I)") (class "Default")
      (node (ref "E7") (pin "3") (pinfunction "I_3") (pintype "input"))
      (node (ref "E8") (pin "8") (pinfunction "O_8") (pintype "output"))
    )
    (net (code "113") (name "Net-(E7B-O)") (class "Default")
      (node (ref "E7") (pin "4") (pinfunction "O_4") (pintype "output"))
      (node (ref "JP4") (pin "5") (pinfunction "5_5") (pintype "passive"))
    )
    (net (code "114") (name "Net-(E8B-O)") (class "Default")
      (node (ref "E8") (pin "6") (pinfunction "O_6") (pintype "output"))
      (node (ref "JP4") (pin "1") (pinfunction "1_1") (pintype "passive"))
    )
    (net (code "115") (name "Net-(E8D-I1)") (class "Default")
      (node (ref "E8") (pin "13") (pinfunction "I1_13") (pintype "input"))
      (node (ref "JP4") (pin "2") (pinfunction "2_2") (pintype "passive"))
      (node (ref "JP4") (pin "4") (pinfunction "4_4") (pintype "passive"))
      (node (ref "JP4") (pin "6") (pinfunction "6_6") (pintype "passive"))
    )
    (net (code "116") (name "Net-(E10A-~{Q})") (class "Default")
      (node (ref "E10") (pin "6") (pinfunction "~{Q}_6") (pintype "output"))
      (node (ref "E4") (pin "17") (pinfunction "A4_17") (pintype "input"))
    )
    (net (code "117") (name "Net-(E10B-PRE)") (class "Default")
      (node (ref "E10") (pin "10") (pinfunction "PRE_10") (pintype "input"))
      (node (ref "E16") (pin "12") (pinfunction "O_12") (pintype "output"))
    )
    (net (code "118") (name "Net-(E10B-~{Q})") (class "Default")
      (node (ref "E10") (pin "8") (pinfunction "~{Q}_8") (pintype "output"))
      (node (ref "E4") (pin "15") (pinfunction "A3_15") (pintype "input"))
    )
    (net (code "119") (name "Net-(E11A-I0)") (class "Default")
      (node (ref "E11") (pin "1") (pinfunction "I0_1") (pintype "input"))
      (node (ref "JP1") (pin "2") (pinfunction "2_2") (pintype "passive"))
      (node (ref "JP1") (pin "4") (pinfunction "4_4") (pintype "passive"))
    )
    (net (code "120") (name "Net-(E11A-I1)") (class "Default")
      (node (ref "E11") (pin "2") (pinfunction "I1_2") (pintype "input"))
      (node (ref "JP2") (pin "2") (pinfunction "2_2") (pintype "passive"))
      (node (ref "JP2") (pin "4") (pinfunction "4_4") (pintype "passive"))
      (node (ref "JP2") (pin "6") (pinfunction "6_6") (pintype "passive"))
    )
    (net (code "121") (name "Net-(E11A-I2)") (class "Default")
      (node (ref "E11") (pin "13") (pinfunction "I2_13") (pintype "input"))
      (node (ref "JP3") (pin "2") (pinfunction "2_2") (pintype "passive"))
      (node (ref "JP3") (pin "4") (pinfunction "4_4") (pintype "passive"))
    )
    (net (code "122") (name "Net-(E11A-O)") (class "Default")
      (node (ref "E11") (pin "12") (pinfunction "O_12") (pintype "output"))
      (node (ref "E8") (pin "12") (pinfunction "I0_12") (pintype "input"))
    )
    (net (code "123") (name "Net-(E13A-~{Q})") (class "Default")
      (node (ref "E13") (pin "6") (pinfunction "~{Q}_6") (pintype "output"))
      (node (ref "E4") (pin "13") (pinfunction "A2_13") (pintype "input"))
    )
    (net (code "124") (name "Net-(E13B-PRE)") (class "Default")
      (node (ref "E13") (pin "10") (pinfunction "PRE_10") (pintype "input"))
      (node (ref "E16") (pin "6") (pinfunction "O_6") (pintype "output"))
    )
    (net (code "125") (name "Net-(E13B-~{Q})") (class "Default")
      (node (ref "E13") (pin "8") (pinfunction "~{Q}_8") (pintype "output"))
      (node (ref "E4") (pin "11") (pinfunction "A1_11") (pintype "input"))
    )
    (net (code "126") (name "Net-(E14B-Y2)") (class "Default")
      (node (ref "E14") (pin "7") (pinfunction "Y2_7") (pintype "tri_state"))
      (node (ref "E19") (pin "2") (pinfunction "I1_2") (pintype "input"))
      (node (ref "E19") (pin "7") (pinfunction "I1_7") (pintype "input"))
      (node (ref "E20") (pin "2") (pinfunction "I1_2") (pintype "input"))
      (node (ref "E20") (pin "7") (pinfunction "I1_7") (pintype "input"))
      (node (ref "E25") (pin "2") (pinfunction "I1_2") (pintype "input"))
      (node (ref "E25") (pin "7") (pinfunction "I1_7") (pintype "input"))
      (node (ref "E26") (pin "2") (pinfunction "I1_2") (pintype "input"))
      (node (ref "E26") (pin "7") (pinfunction "I1_7") (pintype "input"))
      (node (ref "E27") (pin "2") (pinfunction "I1_2") (pintype "input"))
      (node (ref "E27") (pin "7") (pinfunction "I1_7") (pintype "input"))
      (node (ref "E32") (pin "2") (pinfunction "I1_2") (pintype "input"))
      (node (ref "E32") (pin "7") (pinfunction "I1_7") (pintype "input"))
    )
    (net (code "127") (name "Net-(E14B-Y3)") (class "Default")
      (node (ref "E14") (pin "5") (pinfunction "Y3_5") (pintype "tri_state"))
      (node (ref "E17") (pin "10") (pinfunction "PRE_10") (pintype "input"))
      (node (ref "E17") (pin "4") (pinfunction "PRE_4") (pintype "input"))
      (node (ref "E18") (pin "10") (pinfunction "PRE_10") (pintype "input"))
      (node (ref "E18") (pin "4") (pinfunction "PRE_4") (pintype "input"))
      (node (ref "E2") (pin "10") (pinfunction "PRE_10") (pintype "input"))
      (node (ref "E2") (pin "4") (pinfunction "PRE_4") (pintype "input"))
      (node (ref "E42") (pin "10") (pinfunction "PRE_10") (pintype "input"))
      (node (ref "E42") (pin "4") (pinfunction "PRE_4") (pintype "input"))
      (node (ref "E43") (pin "10") (pinfunction "PRE_10") (pintype "input"))
      (node (ref "E43") (pin "4") (pinfunction "PRE_4") (pintype "input"))
      (node (ref "E5") (pin "10") (pinfunction "PRE_10") (pintype "input"))
      (node (ref "E5") (pin "4") (pinfunction "PRE_4") (pintype "input"))
    )
    (net (code "128") (name "Net-(E15E-I)") (class "Default")
      (node (ref "E15") (pin "11") (pinfunction "I_11") (pintype "input"))
      (node (ref "PAD12") (pin "1") (pinfunction "P_1") (pintype "passive"))
    )
    (net (code "129") (name "Net-(E15E-O)") (class "Default")
      (node (ref "E15") (pin "10") (pinfunction "O_10") (pintype "output"))
      (node (ref "PAD13") (pin "1") (pinfunction "P_1") (pintype "passive"))
    )
    (net (code "130") (name "Net-(E15F-I)") (class "Default")
      (node (ref "E15") (pin "13") (pinfunction "I_13") (pintype "input"))
      (node (ref "PAD14") (pin "1") (pinfunction "P_1") (pintype "passive"))
    )
    (net (code "131") (name "Net-(E15F-O)") (class "Default")
      (node (ref "E15") (pin "12") (pinfunction "O_12") (pintype "output"))
      (node (ref "PAD15") (pin "1") (pinfunction "P_1") (pintype "passive"))
    )
    (net (code "132") (name "Net-(E16C-I0)") (class "Default")
      (node (ref "E16") (pin "9") (pinfunction "I0_9") (pintype "input"))
      (node (ref "PAD27") (pin "1") (pinfunction "P_1") (pintype "passive"))
    )
    (net (code "133") (name "Net-(E16C-I1)") (class "Default")
      (node (ref "E16") (pin "10") (pinfunction "I1_10") (pintype "input"))
      (node (ref "PAD28") (pin "1") (pinfunction "P_1") (pintype "passive"))
    )
    (net (code "134") (name "Net-(E16C-I2)") (class "Default")
      (node (ref "E16") (pin "11") (pinfunction "I2_11") (pintype "input"))
      (node (ref "PAD29") (pin "1") (pinfunction "P_1") (pintype "passive"))
    )
    (net (code "135") (name "Net-(E16C-O)") (class "Default")
      (node (ref "E16") (pin "8") (pinfunction "O_8") (pintype "output"))
      (node (ref "PAD30") (pin "1") (pinfunction "P_1") (pintype "passive"))
    )
    (net (code "136") (name "Net-(E17A-CLK)") (class "Default")
      (node (ref "E17") (pin "11") (pinfunction "CLK_11") (pintype "input"))
      (node (ref "E17") (pin "3") (pinfunction "CLK_3") (pintype "input"))
      (node (ref "E18") (pin "11") (pinfunction "CLK_11") (pintype "input"))
      (node (ref "E18") (pin "3") (pinfunction "CLK_3") (pintype "input"))
      (node (ref "E39") (pin "6") (pinfunction "O_6") (pintype "output"))
    )
    (net (code "137") (name "Net-(E17A-~{Q})") (class "Default")
      (node (ref "E17") (pin "6") (pinfunction "~{Q}_6") (pintype "output"))
      (node (ref "E26") (pin "6") (pinfunction "I0_6") (pintype "input"))
    )
    (net (code "138") (name "Net-(E17B-~{Q})") (class "Default")
      (node (ref "E17") (pin "8") (pinfunction "~{Q}_8") (pintype "output"))
      (node (ref "E26") (pin "1") (pinfunction "I0_1") (pintype "input"))
    )
    (net (code "139") (name "Net-(E18A-~{Q})") (class "Default")
      (node (ref "E18") (pin "6") (pinfunction "~{Q}_6") (pintype "output"))
      (node (ref "E27") (pin "6") (pinfunction "I0_6") (pintype "input"))
    )
    (net (code "140") (name "Net-(E18B-~{Q})") (class "Default")
      (node (ref "E18") (pin "8") (pinfunction "~{Q}_8") (pintype "output"))
      (node (ref "E27") (pin "1") (pinfunction "I0_1") (pintype "input"))
    )
    (net (code "141") (name "Net-(E19A-I0)") (class "Default")
      (node (ref "E19") (pin "1") (pinfunction "I0_1") (pintype "input"))
      (node (ref "E43") (pin "8") (pinfunction "~{Q}_8") (pintype "output"))
    )
    (net (code "142") (name "Net-(E19B-I0)") (class "Default")
      (node (ref "E19") (pin "6") (pinfunction "I0_6") (pintype "input"))
      (node (ref "E43") (pin "6") (pinfunction "~{Q}_6") (pintype "output"))
    )
    (net (code "143") (name "Net-(E20A-I0)") (class "Default")
      (node (ref "E20") (pin "1") (pinfunction "I0_1") (pintype "input"))
      (node (ref "E42") (pin "8") (pinfunction "~{Q}_8") (pintype "output"))
    )
    (net (code "144") (name "Net-(E20B-I0)") (class "Default")
      (node (ref "E20") (pin "6") (pinfunction "I0_6") (pintype "input"))
      (node (ref "E42") (pin "6") (pinfunction "~{Q}_6") (pintype "output"))
    )
    (net (code "145") (name "Net-(E21A-I0)") (class "Default")
      (node (ref "E21") (pin "1") (pinfunction "I0_1") (pintype "input"))
      (node (ref "E3") (pin "8") (pinfunction "O_8") (pintype "output"))
    )
    (net (code "146") (name "Net-(E22A-TAP1)") (class "Default")
      (node (ref "E22") (pin "7") (pinfunction "TAP1_7") (pintype "output"))
      (node (ref "E28") (pin "12") (pinfunction "TAP1_12") (pintype "output"))
    )
    (net (code "147") (name "Net-(E22A-TAP2)") (class "Default")
      (node (ref "E22") (pin "2") (pinfunction "TAP2_2") (pintype "output"))
      (node (ref "E23") (pin "12") (pinfunction "I0_12") (pintype "input"))
      (node (ref "E28") (pin "4") (pinfunction "TAP2_4") (pintype "output"))
    )
    (net (code "148") (name "Net-(E22A-TAP3)") (class "Default")
      (node (ref "E22") (pin "6") (pinfunction "TAP3_6") (pintype "output"))
      (node (ref "E23") (pin "1") (pinfunction "I0_1") (pintype "input"))
      (node (ref "E28") (pin "10") (pinfunction "TAP3_10") (pintype "output"))
    )
    (net (code "149") (name "Net-(E22A-TAP4)") (class "Default")
      (node (ref "E22") (pin "3") (pinfunction "TAP4_3") (pintype "output"))
      (node (ref "E28") (pin "6") (pinfunction "TAP4_6") (pintype "output"))
    )
    (net (code "150") (name "Net-(E22A-TAP5)") (class "Default")
      (node (ref "E22") (pin "5") (pinfunction "TAP5_5") (pintype "output"))
      (node (ref "E28") (pin "8") (pinfunction "TAP5_8") (pintype "output"))
    )
    (net (code "151") (name "Net-(E23A-I1)") (class "Default")
      (node (ref "E23") (pin "2") (pinfunction "I1_2") (pintype "input"))
      (node (ref "E23") (pin "6") (pinfunction "O_6") (pintype "output"))
      (node (ref "E24") (pin "4") (pinfunction "A2_4") (pintype "input"))
    )
    (net (code "152") (name "Net-(E23A-O)") (class "Default")
      (node (ref "C4") (pin "1") (pinfunction "1_1") (pintype "passive"))
      (node (ref "E23") (pin "3") (pinfunction "O_3") (pintype "output"))
      (node (ref "R28") (pin "1") (pinfunction "1_1") (pintype "passive"))
    )
    (net (code "153") (name "Net-(E23B-I0)") (class "Default")
      (node (ref "C4") (pin "2") (pinfunction "2_2") (pintype "passive"))
      (node (ref "D4") (pin "C") (pinfunction "C_C") (pintype "passive"))
      (node (ref "E23") (pin "4") (pinfunction "I0_4") (pintype "input"))
      (node (ref "E23") (pin "5") (pinfunction "I1_5") (pintype "input"))
      (node (ref "R27") (pin "2") (pinfunction "2_2") (pintype "passive"))
    )
    (net (code "154") (name "Net-(E23C-I0)") (class "Default")
      (node (ref "C3") (pin "2") (pinfunction "2_2") (pintype "passive"))
      (node (ref "D3") (pin "C") (pinfunction "C_C") (pintype "passive"))
      (node (ref "E23") (pin "10") (pinfunction "I1_10") (pintype "input"))
      (node (ref "E23") (pin "9") (pinfunction "I0_9") (pintype "input"))
      (node (ref "R25") (pin "2") (pinfunction "2_2") (pintype "passive"))
    )
    (net (code "155") (name "Net-(E23C-O)") (class "Default")
      (node (ref "E23") (pin "13") (pinfunction "I1_13") (pintype "input"))
      (node (ref "E23") (pin "8") (pinfunction "O_8") (pintype "output"))
      (node (ref "E24") (pin "2") (pinfunction "A1_2") (pintype "input"))
    )
    (net (code "156") (name "Net-(E23D-O)") (class "Default")
      (node (ref "C3") (pin "1") (pinfunction "1_1") (pintype "passive"))
      (node (ref "E23") (pin "11") (pinfunction "O_11") (pintype "output"))
      (node (ref "R26") (pin "1") (pinfunction "1_1") (pintype "passive"))
    )
    (net (code "157") (name "Net-(E24A-A3)") (class "Default")
      (node (ref "E24") (pin "6") (pinfunction "A3_6") (pintype "input"))
      (node (ref "E29") (pin "2") (pinfunction "I1_2") (pintype "input"))
      (node (ref "E29") (pin "6") (pinfunction "O_6") (pintype "output"))
    )
    (net (code "158") (name "Net-(E24B-A1)") (class "Default")
      (node (ref "E24") (pin "11") (pinfunction "A1_11") (pintype "input"))
      (node (ref "E31") (pin "13") (pinfunction "I1_13") (pintype "input"))
      (node (ref "E31") (pin "8") (pinfunction "O_8") (pintype "output"))
    )
    (net (code "159") (name "Net-(E24B-A2)") (class "Default")
      (node (ref "E24") (pin "13") (pinfunction "A2_13") (pintype "input"))
      (node (ref "E31") (pin "2") (pinfunction "I1_2") (pintype "input"))
      (node (ref "E31") (pin "6") (pinfunction "O_6") (pintype "output"))
    )
    (net (code "160") (name "Net-(E25A-I0)") (class "Default")
      (node (ref "E2") (pin "8") (pinfunction "~{Q}_8") (pintype "output"))
      (node (ref "E25") (pin "1") (pinfunction "I0_1") (pintype "input"))
    )
    (net (code "161") (name "Net-(E25B-I0)") (class "Default")
      (node (ref "E2") (pin "6") (pinfunction "~{Q}_6") (pintype "output"))
      (node (ref "E25") (pin "6") (pinfunction "I0_6") (pintype "input"))
    )
    (net (code "162") (name "Net-(E29A-O)") (class "Default")
      (node (ref "C5") (pin "1") (pinfunction "1_1") (pintype "passive"))
      (node (ref "E29") (pin "3") (pinfunction "O_3") (pintype "output"))
      (node (ref "R30") (pin "1") (pinfunction "1_1") (pintype "passive"))
    )
    (net (code "163") (name "Net-(E29B-I0)") (class "Default")
      (node (ref "C5") (pin "2") (pinfunction "2_2") (pintype "passive"))
      (node (ref "D5") (pin "C") (pinfunction "C_C") (pintype "passive"))
      (node (ref "E29") (pin "4") (pinfunction "I0_4") (pintype "input"))
      (node (ref "E29") (pin "5") (pinfunction "I1_5") (pintype "input"))
      (node (ref "R29") (pin "2") (pinfunction "2_2") (pintype "passive"))
    )
    (net (code "164") (name "Net-(E29C-I0)") (class "Default")
      (node (ref "E29") (pin "9") (pinfunction "I0_9") (pintype "input"))
      (node (ref "PAD31") (pin "1") (pinfunction "P_1") (pintype "passive"))
    )
    (net (code "165") (name "Net-(E29C-I1)") (class "Default")
      (node (ref "E29") (pin "10") (pinfunction "I1_10") (pintype "input"))
      (node (ref "PAD32") (pin "1") (pinfunction "P_1") (pintype "passive"))
    )
    (net (code "166") (name "Net-(E29C-O)") (class "Default")
      (node (ref "E29") (pin "8") (pinfunction "O_8") (pintype "output"))
      (node (ref "PAD33") (pin "1") (pinfunction "P_1") (pintype "passive"))
    )
    (net (code "167") (name "Net-(E29D-I0)") (class "Default")
      (node (ref "E29") (pin "12") (pinfunction "I0_12") (pintype "input"))
      (node (ref "PAD34") (pin "1") (pinfunction "P_1") (pintype "passive"))
    )
    (net (code "168") (name "Net-(E29D-I1)") (class "Default")
      (node (ref "E29") (pin "13") (pinfunction "I1_13") (pintype "input"))
      (node (ref "PAD35") (pin "1") (pinfunction "P_1") (pintype "passive"))
    )
    (net (code "169") (name "Net-(E29D-O)") (class "Default")
      (node (ref "E29") (pin "11") (pinfunction "O_11") (pintype "output"))
      (node (ref "PAD36") (pin "1") (pinfunction "P_1") (pintype "passive"))
    )
    (net (code "170") (name "Net-(E30G-IN)") (class "Default")
      (node (ref "E3") (pin "12") (pinfunction "O_12") (pintype "output"))
      (node (ref "E30") (pin "1") (pinfunction "IN_1") (pintype "input"))
      (node (ref "E35") (pin "1") (pinfunction "IN_1") (pintype "input"))
    )
    (net (code "171") (name "Net-(E30G-TAP1)") (class "Default")
      (node (ref "E30") (pin "12") (pinfunction "TAP1_12") (pintype "output"))
      (node (ref "E31") (pin "12") (pinfunction "I0_12") (pintype "input"))
      (node (ref "E35") (pin "7") (pinfunction "TAP1_7") (pintype "output"))
    )
    (net (code "172") (name "Net-(E30G-TAP2)") (class "Default")
      (node (ref "E30") (pin "4") (pinfunction "TAP2_4") (pintype "output"))
      (node (ref "E35") (pin "2") (pinfunction "TAP2_2") (pintype "output"))
    )
    (net (code "173") (name "Net-(E30G-TAP3)") (class "Default")
      (node (ref "E30") (pin "10") (pinfunction "TAP3_10") (pintype "output"))
      (node (ref "E35") (pin "6") (pinfunction "TAP3_6") (pintype "output"))
    )
    (net (code "174") (name "Net-(E30G-TAP4)") (class "Default")
      (node (ref "E30") (pin "6") (pinfunction "TAP4_6") (pintype "output"))
      (node (ref "E31") (pin "1") (pinfunction "I0_1") (pintype "input"))
      (node (ref "E35") (pin "3") (pinfunction "TAP4_3") (pintype "output"))
    )
    (net (code "175") (name "Net-(E30G-TAP5)") (class "Default")
      (node (ref "E30") (pin "8") (pinfunction "TAP5_8") (pintype "output"))
      (node (ref "E35") (pin "5") (pinfunction "TAP5_5") (pintype "output"))
    )
    (net (code "176") (name "Net-(E31A-O)") (class "Default")
      (node (ref "C2") (pin "1") (pinfunction "1_1") (pintype "passive"))
      (node (ref "E31") (pin "3") (pinfunction "O_3") (pintype "output"))
      (node (ref "R22") (pin "1") (pinfunction "1_1") (pintype "passive"))
    )
    (net (code "177") (name "Net-(E31B-I0)") (class "Default")
      (node (ref "C2") (pin "2") (pinfunction "2_2") (pintype "passive"))
      (node (ref "D2") (pin "C") (pinfunction "C_C") (pintype "passive"))
      (node (ref "E31") (pin "4") (pinfunction "I0_4") (pintype "input"))
      (node (ref "E31") (pin "5") (pinfunction "I1_5") (pintype "input"))
      (node (ref "R21") (pin "2") (pinfunction "2_2") (pintype "passive"))
    )
    (net (code "178") (name "Net-(E31C-I0)") (class "Default")
      (node (ref "C1") (pin "2") (pinfunction "2_2") (pintype "passive"))
      (node (ref "D1") (pin "C") (pinfunction "C_C") (pintype "passive"))
      (node (ref "E31") (pin "10") (pinfunction "I1_10") (pintype "input"))
      (node (ref "E31") (pin "9") (pinfunction "I0_9") (pintype "input"))
      (node (ref "R19") (pin "2") (pinfunction "2_2") (pintype "passive"))
    )
    (net (code "179") (name "Net-(E31D-O)") (class "Default")
      (node (ref "C1") (pin "1") (pinfunction "1_1") (pintype "passive"))
      (node (ref "E31") (pin "11") (pinfunction "O_11") (pintype "output"))
      (node (ref "R20") (pin "1") (pinfunction "1_1") (pintype "passive"))
    )
    (net (code "180") (name "Net-(E32A-I0)") (class "Default")
      (node (ref "E32") (pin "1") (pinfunction "I0_1") (pintype "input"))
      (node (ref "E5") (pin "8") (pinfunction "~{Q}_8") (pintype "output"))
    )
    (net (code "181") (name "Net-(E32B-I0)") (class "Default")
      (node (ref "E32") (pin "6") (pinfunction "I0_6") (pintype "input"))
      (node (ref "E5") (pin "6") (pinfunction "~{Q}_6") (pintype "output"))
    )
    (net (code "182") (name "Net-(E39C-O)") (class "Default")
      (node (ref "E39") (pin "8") (pinfunction "O_8") (pintype "output"))
      (node (ref "E42") (pin "11") (pinfunction "CLK_11") (pintype "input"))
      (node (ref "E42") (pin "3") (pinfunction "CLK_3") (pintype "input"))
      (node (ref "E43") (pin "11") (pinfunction "CLK_11") (pintype "input"))
      (node (ref "E43") (pin "3") (pinfunction "CLK_3") (pintype "input"))
    )
    (net (code "183") (name "Net-(E39D-I0)") (class "Default")
      (node (ref "E39") (pin "12") (pinfunction "I0_12") (pintype "input"))
      (node (ref "PAD42") (pin "1") (pinfunction "P_1") (pintype "passive"))
    )
    (net (code "184") (name "Net-(E39D-I1)") (class "Default")
      (node (ref "E39") (pin "13") (pinfunction "I1_13") (pintype "input"))
      (node (ref "PAD43") (pin "1") (pinfunction "P_1") (pintype "passive"))
    )
    (net (code "185") (name "Net-(E39D-O)") (class "Default")
      (node (ref "E39") (pin "11") (pinfunction "O_11") (pintype "output"))
      (node (ref "PAD44") (pin "1") (pinfunction "P_1") (pintype "passive"))
    )
    (net (code "186") (name "VCC") (class "Default")
      (node (ref "C10") (pin "1") (pinfunction "1_1") (pintype "passive"))
      (node (ref "C11") (pin "1") (pinfunction "1_1") (pintype "passive"))
      (node (ref "C12") (pin "1") (pinfunction "1_1") (pintype "passive"))
      (node (ref "C13") (pin "1") (pinfunction "1_1") (pintype "passive"))
      (node (ref "C14") (pin "1") (pinfunction "1_1") (pintype "passive"))
      (node (ref "C15") (pin "1") (pinfunction "1_1") (pintype "passive"))
      (node (ref "C16") (pin "1") (pinfunction "1_1") (pintype "passive"))
      (node (ref "C17") (pin "1") (pinfunction "1_1") (pintype "passive"))
      (node (ref "C18") (pin "1") (pinfunction "1_1") (pintype "passive"))
      (node (ref "C19") (pin "1") (pinfunction "1_1") (pintype "passive"))
      (node (ref "C20") (pin "1") (pinfunction "1_1") (pintype "passive"))
      (node (ref "C21") (pin "1") (pinfunction "1_1") (pintype "passive"))
      (node (ref "C22") (pin "1") (pinfunction "1_1") (pintype "passive"))
      (node (ref "C23") (pin "1") (pinfunction "1_1") (pintype "passive"))
      (node (ref "C24") (pin "1") (pinfunction "1_1") (pintype "passive"))
      (node (ref "C25") (pin "1") (pinfunction "1_1") (pintype "passive"))
      (node (ref "C26") (pin "1") (pinfunction "1_1") (pintype "passive"))
      (node (ref "C27") (pin "1") (pinfunction "1_1") (pintype "passive"))
      (node (ref "C28") (pin "1") (pinfunction "1_1") (pintype "passive"))
      (node (ref "C29") (pin "1") (pinfunction "1_1") (pintype "passive"))
      (node (ref "C30") (pin "1") (pinfunction "1_1") (pintype "passive"))
      (node (ref "C31") (pin "1") (pinfunction "1_1") (pintype "passive"))
      (node (ref "C32") (pin "1") (pinfunction "1_1") (pintype "passive"))
      (node (ref "C33") (pin "1") (pinfunction "1_1") (pintype "passive"))
      (node (ref "C34") (pin "1") (pinfunction "1_1") (pintype "passive"))
      (node (ref "C35") (pin "1") (pinfunction "1_1") (pintype "passive"))
      (node (ref "C36") (pin "1") (pinfunction "1_1") (pintype "passive"))
      (node (ref "C37") (pin "1") (pinfunction "1_1") (pintype "passive"))
      (node (ref "C38") (pin "1") (pinfunction "1_1") (pintype "passive"))
      (node (ref "C39") (pin "1") (pinfunction "1_1") (pintype "passive"))
      (node (ref "C40") (pin "1") (pinfunction "1_1") (pintype "passive"))
      (node (ref "C41") (pin "1") (pinfunction "1_1") (pintype "passive"))
      (node (ref "C42") (pin "1") (pinfunction "1_1") (pintype "passive"))
      (node (ref "C43") (pin "1") (pinfunction "1_1") (pintype "passive"))
      (node (ref "C44") (pin "1") (pinfunction "1_1") (pintype "passive"))
      (node (ref "C45") (pin "1") (pinfunction "1_1") (pintype "passive"))
      (node (ref "C46") (pin "1") (pinfunction "1_1") (pintype "passive"))
      (node (ref "C47") (pin "1") (pinfunction "1_1") (pintype "passive"))
      (node (ref "C48") (pin "1") (pinfunction "1_1") (pintype "passive"))
      (node (ref "C49") (pin "+") (pinfunction "+_+") (pintype "passive"))
      (node (ref "C50") (pin "+") (pinfunction "+_+") (pintype "passive"))
      (node (ref "C51") (pin "+") (pinfunction "+_+") (pintype "passive"))
      (node (ref "C52") (pin "+") (pinfunction "+_+") (pintype "passive"))
      (node (ref "C6") (pin "1") (pinfunction "1_1") (pintype "passive"))
      (node (ref "C7") (pin "1") (pinfunction "1_1") (pintype "passive"))
      (node (ref "C8") (pin "1") (pinfunction "1_1") (pintype "passive"))
      (node (ref "C9") (pin "1") (pinfunction "1_1") (pintype "passive"))
      (node (ref "R11") (pin "1") (pinfunction "1_1") (pintype "passive"))
      (node (ref "R15") (pin "1") (pinfunction "1_1") (pintype "passive"))
      (node (ref "R17") (pin "1") (pinfunction "1_1") (pintype "passive"))
      (node (ref "R20") (pin "2") (pinfunction "2_2") (pintype "passive"))
      (node (ref "R22") (pin "2") (pinfunction "2_2") (pintype "passive"))
      (node (ref "R26") (pin "2") (pinfunction "2_2") (pintype "passive"))
      (node (ref "R28") (pin "2") (pinfunction "2_2") (pintype "passive"))
      (node (ref "R30") (pin "2") (pinfunction "2_2") (pintype "passive"))
      (node (ref "U$1") (pin "AA2") (pinfunction "1_AA2") (pintype "bidirectional"))
      (node (ref "U$1") (pin "BA2") (pinfunction "1_BA2") (pintype "bidirectional"))
      (node (ref "U$1") (pin "CA2") (pinfunction "1_CA2") (pintype "bidirectional"))
      (node (ref "U$1") (pin "DA2") (pinfunction "1_DA2") (pintype "bidirectional"))
    )
    (net (code "187") (name "unconnected-(E1A-Y4-Pad12)") (class "Default")
      (node (ref "E1") (pin "12") (pinfunction "Y4_12") (pintype "tri_state"))
    )
    (net (code "188") (name "unconnected-(E2A-Q-Pad5)") (class "Default")
      (node (ref "E2") (pin "5") (pinfunction "Q_5") (pintype "output"))
    )
    (net (code "189") (name "unconnected-(E2B-Q-Pad9)") (class "Default")
      (node (ref "E2") (pin "9") (pinfunction "Q_9") (pintype "output"))
    )
    (net (code "190") (name "unconnected-(E4A-Y3-Pad14)") (class "Default")
      (node (ref "E4") (pin "14") (pinfunction "Y3_14") (pintype "tri_state"))
    )
    (net (code "191") (name "unconnected-(E4A-Y4-Pad12)") (class "Default")
      (node (ref "E4") (pin "12") (pinfunction "Y4_12") (pintype "tri_state"))
    )
    (net (code "192") (name "unconnected-(E5A-Q-Pad5)") (class "Default")
      (node (ref "E5") (pin "5") (pinfunction "Q_5") (pintype "output"))
    )
    (net (code "193") (name "unconnected-(E5B-Q-Pad9)") (class "Default")
      (node (ref "E5") (pin "9") (pinfunction "Q_9") (pintype "output"))
    )
    (net (code "194") (name "unconnected-(E6A-Q-Pad5)") (class "Default")
      (node (ref "E6") (pin "5") (pinfunction "Q_5") (pintype "output"))
    )
    (net (code "195") (name "unconnected-(E6B-Q-Pad9)") (class "Default")
      (node (ref "E6") (pin "9") (pinfunction "Q_9") (pintype "output"))
    )
    (net (code "196") (name "unconnected-(E9A-Q-Pad5)") (class "Default")
      (node (ref "E9") (pin "5") (pinfunction "Q_5") (pintype "output"))
    )
    (net (code "197") (name "unconnected-(E9B-Q-Pad9)") (class "Default")
      (node (ref "E9") (pin "9") (pinfunction "Q_9") (pintype "output"))
    )
    (net (code "198") (name "unconnected-(E10A-Q-Pad5)") (class "Default")
      (node (ref "E10") (pin "5") (pinfunction "Q_5") (pintype "output"))
    )
    (net (code "199") (name "unconnected-(E10B-Q-Pad9)") (class "Default")
      (node (ref "E10") (pin "9") (pinfunction "Q_9") (pintype "output"))
    )
    (net (code "200") (name "unconnected-(E13B-Q-Pad9)") (class "Default")
      (node (ref "E13") (pin "9") (pinfunction "Q_9") (pintype "output"))
    )
    (net (code "201") (name "unconnected-(E14B-Y4-Pad3)") (class "Default")
      (node (ref "E14") (pin "3") (pinfunction "Y4_3") (pintype "tri_state"))
    )
    (net (code "202") (name "unconnected-(E17A-Q-Pad5)") (class "Default")
      (node (ref "E17") (pin "5") (pinfunction "Q_5") (pintype "output"))
    )
    (net (code "203") (name "unconnected-(E17B-Q-Pad9)") (class "Default")
      (node (ref "E17") (pin "9") (pinfunction "Q_9") (pintype "output"))
    )
    (net (code "204") (name "unconnected-(E18A-Q-Pad5)") (class "Default")
      (node (ref "E18") (pin "5") (pinfunction "Q_5") (pintype "output"))
    )
    (net (code "205") (name "unconnected-(E18B-Q-Pad9)") (class "Default")
      (node (ref "E18") (pin "9") (pinfunction "Q_9") (pintype "output"))
    )
    (net (code "206") (name "unconnected-(E24A-Y4-Pad12)") (class "Default")
      (node (ref "E24") (pin "12") (pinfunction "Y4_12") (pintype "tri_state"))
    )
    (net (code "207") (name "unconnected-(E24B-Y3-Pad5)") (class "Default")
      (node (ref "E24") (pin "5") (pinfunction "Y3_5") (pintype "tri_state"))
    )
    (net (code "208") (name "unconnected-(E24B-Y4-Pad3)") (class "Default")
      (node (ref "E24") (pin "3") (pinfunction "Y4_3") (pintype "tri_state"))
    )
    (net (code "209") (name "unconnected-(E42A-Q-Pad5)") (class "Default")
      (node (ref "E42") (pin "5") (pinfunction "Q_5") (pintype "output"))
    )
    (net (code "210") (name "unconnected-(E42B-Q-Pad9)") (class "Default")
      (node (ref "E42") (pin "9") (pinfunction "Q_9") (pintype "output"))
    )
    (net (code "211") (name "unconnected-(E43A-Q-Pad5)") (class "Default")
      (node (ref "E43") (pin "5") (pinfunction "Q_5") (pintype "output"))
    )
    (net (code "212") (name "unconnected-(E43B-Q-Pad9)") (class "Default")
      (node (ref "E43") (pin "9") (pinfunction "Q_9") (pintype "output"))
    )
    (net (code "213") (name "unconnected-(H01/H20-Pad2)") (class "Default")
      (node (ref "H01/H20") (pin "2") (pinfunction "2_2") (pintype "passive"))
    )
    (net (code "214") (name "unconnected-(H01/H20-Pad4)") (class "Default")
      (node (ref "H01/H20") (pin "4") (pinfunction "4_4") (pintype "passive"))
    )
    (net (code "215") (name "unconnected-(H01/H20-Pad10)") (class "Default")
      (node (ref "H01/H20") (pin "10") (pinfunction "10_10") (pintype "passive"))
    )
    (net (code "216") (name "unconnected-(H01/H20-Pad14)") (class "Default")
      (node (ref "H01/H20") (pin "14") (pinfunction "14_14") (pintype "passive"))
    )
    (net (code "217") (name "unconnected-(H01/H20-Pad18)") (class "Default")
      (node (ref "H01/H20") (pin "18") (pinfunction "18_18") (pintype "passive"))
    )
    (net (code "218") (name "unconnected-(H01/H20-Pad22)") (class "Default")
      (node (ref "H01/H20") (pin "22") (pinfunction "22_22") (pintype "passive"))
    )
    (net (code "219") (name "unconnected-(H01/H20-Pad26)") (class "Default")
      (node (ref "H01/H20") (pin "26") (pinfunction "26_26") (pintype "passive"))
    )
    (net (code "220") (name "unconnected-(H01/H20-Pad34)") (class "Default")
      (node (ref "H01/H20") (pin "34") (pinfunction "34_34") (pintype "passive"))
    )
    (net (code "221") (name "unconnected-(H02/H21-Pad2)") (class "Default")
      (node (ref "H02/H21") (pin "2") (pinfunction "2_2") (pintype "passive"))
    )
    (net (code "222") (name "unconnected-(H02/H21-Pad4)") (class "Default")
      (node (ref "H02/H21") (pin "4") (pinfunction "4_4") (pintype "passive"))
    )
    (net (code "223") (name "unconnected-(H02/H21-Pad10)") (class "Default")
      (node (ref "H02/H21") (pin "10") (pinfunction "10_10") (pintype "passive"))
    )
    (net (code "224") (name "unconnected-(H02/H21-Pad14)") (class "Default")
      (node (ref "H02/H21") (pin "14") (pinfunction "14_14") (pintype "passive"))
    )
    (net (code "225") (name "unconnected-(H02/H21-Pad18)") (class "Default")
      (node (ref "H02/H21") (pin "18") (pinfunction "18_18") (pintype "passive"))
    )
    (net (code "226") (name "unconnected-(H02/H21-Pad22)") (class "Default")
      (node (ref "H02/H21") (pin "22") (pinfunction "22_22") (pintype "passive"))
    )
    (net (code "227") (name "unconnected-(H02/H21-Pad26)") (class "Default")
      (node (ref "H02/H21") (pin "26") (pinfunction "26_26") (pintype "passive"))
    )
    (net (code "228") (name "unconnected-(H02/H21-Pad34)") (class "Default")
      (node (ref "H02/H21") (pin "34") (pinfunction "34_34") (pintype "passive"))
    )
    (net (code "229") (name "unconnected-(H03/H22-Pad2)") (class "Default")
      (node (ref "H03/H22") (pin "2") (pinfunction "2_2") (pintype "passive"))
    )
    (net (code "230") (name "unconnected-(H03/H22-Pad4)") (class "Default")
      (node (ref "H03/H22") (pin "4") (pinfunction "4_4") (pintype "passive"))
    )
    (net (code "231") (name "unconnected-(H03/H22-Pad10)") (class "Default")
      (node (ref "H03/H22") (pin "10") (pinfunction "10_10") (pintype "passive"))
    )
    (net (code "232") (name "unconnected-(H03/H22-Pad14)") (class "Default")
      (node (ref "H03/H22") (pin "14") (pinfunction "14_14") (pintype "passive"))
    )
    (net (code "233") (name "unconnected-(H03/H22-Pad18)") (class "Default")
      (node (ref "H03/H22") (pin "18") (pinfunction "18_18") (pintype "passive"))
    )
    (net (code "234") (name "unconnected-(H03/H22-Pad22)") (class "Default")
      (node (ref "H03/H22") (pin "22") (pinfunction "22_22") (pintype "passive"))
    )
    (net (code "235") (name "unconnected-(H03/H22-Pad26)") (class "Default")
      (node (ref "H03/H22") (pin "26") (pinfunction "26_26") (pintype "passive"))
    )
    (net (code "236") (name "unconnected-(H03/H22-Pad34)") (class "Default")
      (node (ref "H03/H22") (pin "34") (pinfunction "34_34") (pintype "passive"))
    )
    (net (code "237") (name "unconnected-(H04/H23-Pad2)") (class "Default")
      (node (ref "H04/H23") (pin "2") (pinfunction "2_2") (pintype "passive"))
    )
    (net (code "238") (name "unconnected-(H04/H23-Pad4)") (class "Default")
      (node (ref "H04/H23") (pin "4") (pinfunction "4_4") (pintype "passive"))
    )
    (net (code "239") (name "unconnected-(H04/H23-Pad6)") (class "Default")
      (node (ref "H04/H23") (pin "6") (pinfunction "6_6") (pintype "passive"))
    )
    (net (code "240") (name "unconnected-(H04/H23-Pad10)") (class "Default")
      (node (ref "H04/H23") (pin "10") (pinfunction "10_10") (pintype "passive"))
    )
    (net (code "241") (name "unconnected-(H04/H23-Pad14)") (class "Default")
      (node (ref "H04/H23") (pin "14") (pinfunction "14_14") (pintype "passive"))
    )
    (net (code "242") (name "unconnected-(H04/H23-Pad18)") (class "Default")
      (node (ref "H04/H23") (pin "18") (pinfunction "18_18") (pintype "passive"))
    )
    (net (code "243") (name "unconnected-(H04/H23-Pad22)") (class "Default")
      (node (ref "H04/H23") (pin "22") (pinfunction "22_22") (pintype "passive"))
    )
    (net (code "244") (name "unconnected-(H04/H23-Pad26)") (class "Default")
      (node (ref "H04/H23") (pin "26") (pinfunction "26_26") (pintype "passive"))
    )
    (net (code "245") (name "unconnected-(H04/H23-Pad34)") (class "Default")
      (node (ref "H04/H23") (pin "34") (pinfunction "34_34") (pintype "passive"))
    )
    (net (code "246") (name "unconnected-(H05/H24-Pad2)") (class "Default")
      (node (ref "H05/H24") (pin "2") (pinfunction "2_2") (pintype "passive"))
    )
    (net (code "247") (name "unconnected-(H05/H24-Pad4)") (class "Default")
      (node (ref "H05/H24") (pin "4") (pinfunction "4_4") (pintype "passive"))
    )
    (net (code "248") (name "unconnected-(H05/H24-Pad10)") (class "Default")
      (node (ref "H05/H24") (pin "10") (pinfunction "10_10") (pintype "passive"))
    )
    (net (code "249") (name "unconnected-(H05/H24-Pad14)") (class "Default")
      (node (ref "H05/H24") (pin "14") (pinfunction "14_14") (pintype "passive"))
    )
    (net (code "250") (name "unconnected-(H05/H24-Pad18)") (class "Default")
      (node (ref "H05/H24") (pin "18") (pinfunction "18_18") (pintype "passive"))
    )
    (net (code "251") (name "unconnected-(H05/H24-Pad22)") (class "Default")
      (node (ref "H05/H24") (pin "22") (pinfunction "22_22") (pintype "passive"))
    )
    (net (code "252") (name "unconnected-(H05/H24-Pad26)") (class "Default")
      (node (ref "H05/H24") (pin "26") (pinfunction "26_26") (pintype "passive"))
    )
    (net (code "253") (name "unconnected-(H05/H24-Pad30)") (class "Default")
      (node (ref "H05/H24") (pin "30") (pinfunction "30_30") (pintype "passive"))
    )
    (net (code "254") (name "unconnected-(H05/H24-Pad34)") (class "Default")
      (node (ref "H05/H24") (pin "34") (pinfunction "34_34") (pintype "passive"))
    )
  )
)
